# pc_healthypi_5_5.net
KiCad netlist of a schematic drawn in EAGLE
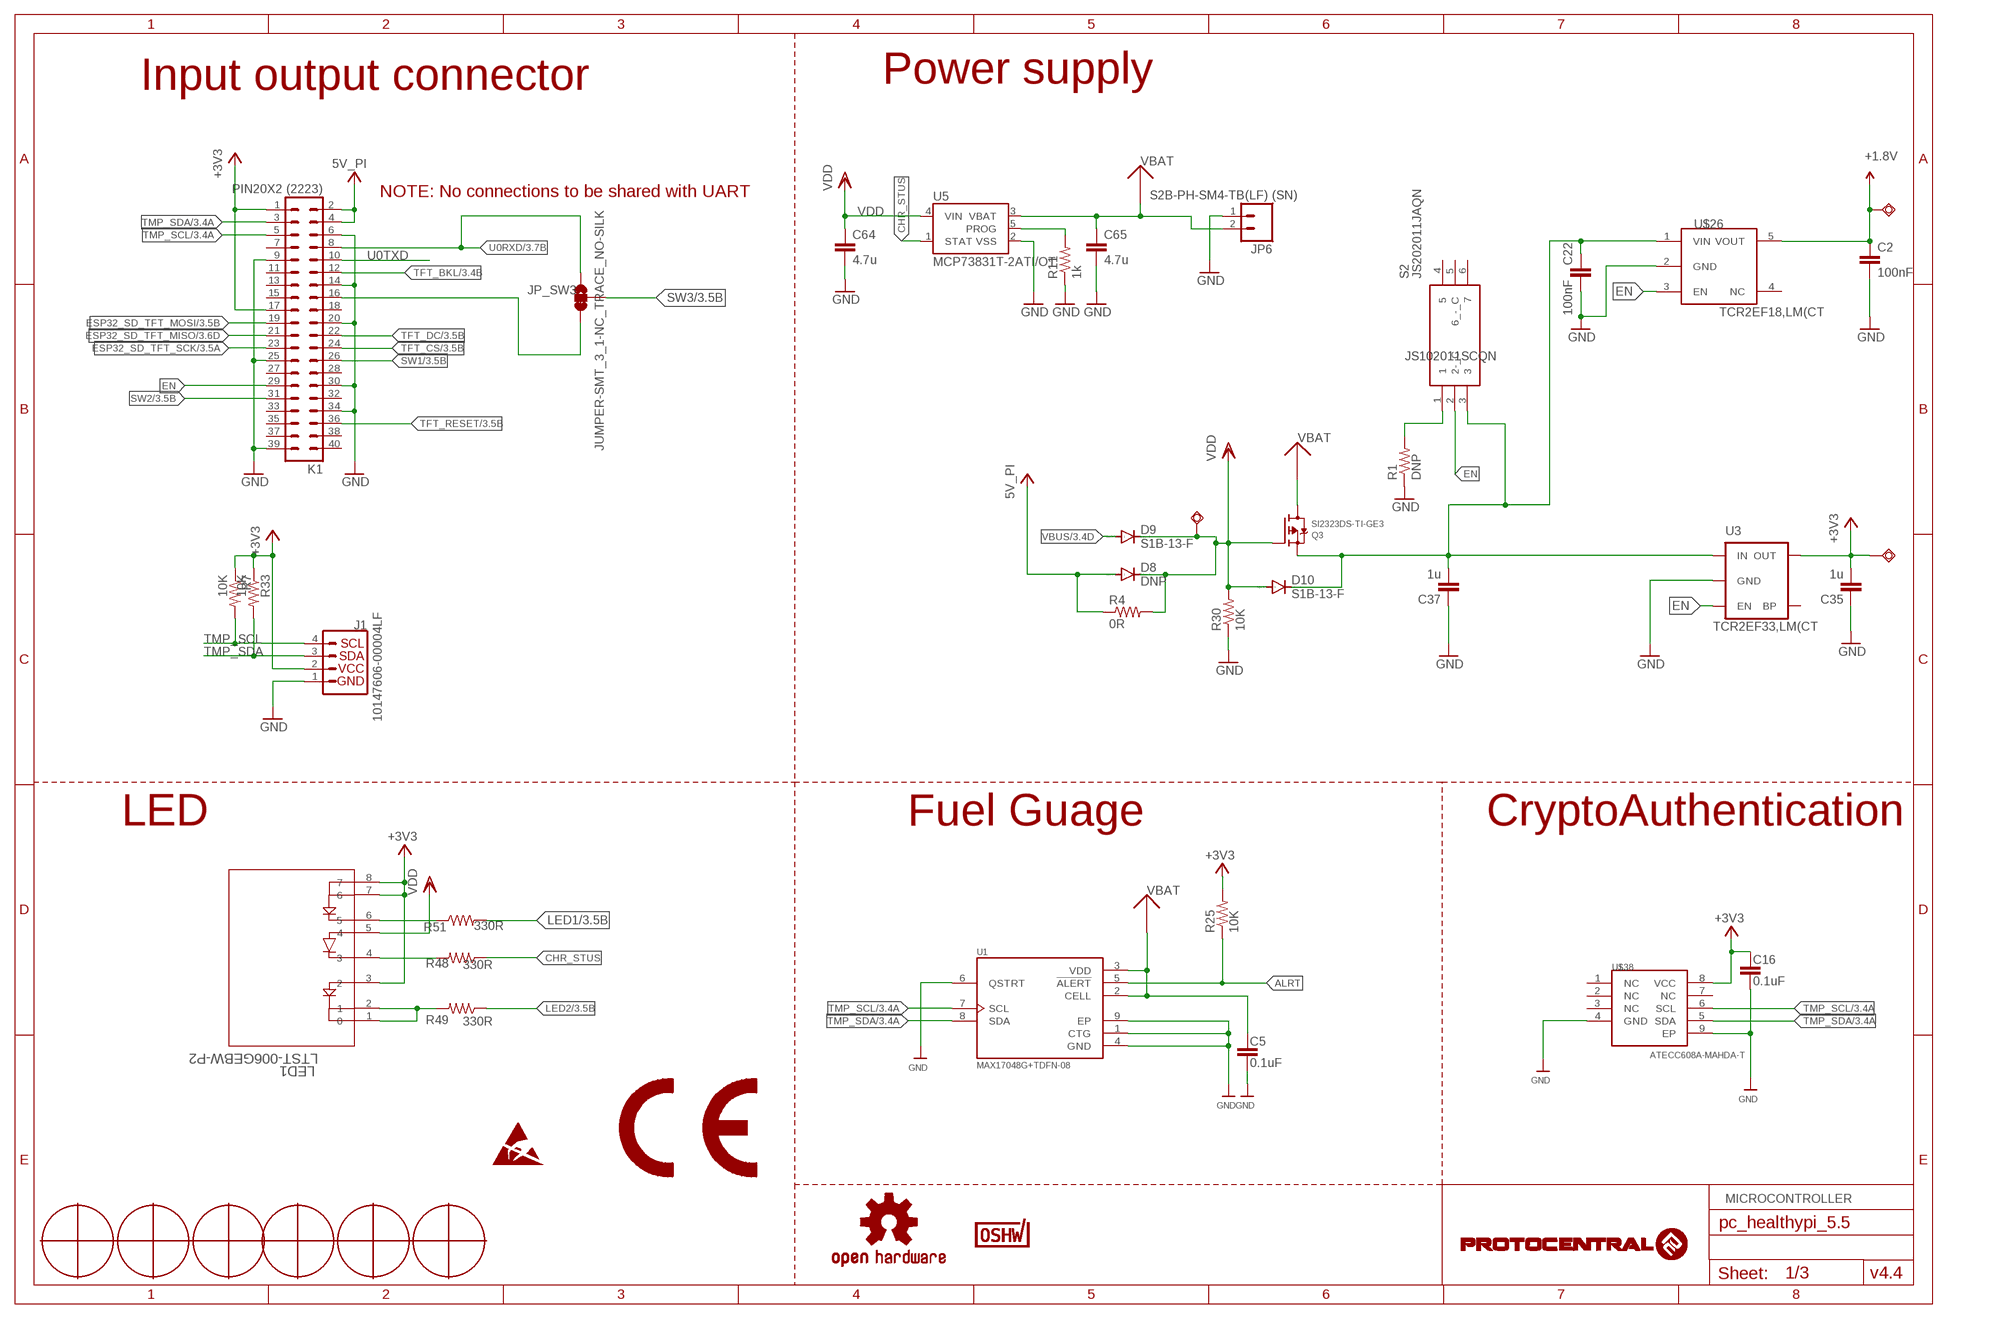
[diagram p0: schematic, sheet 1]
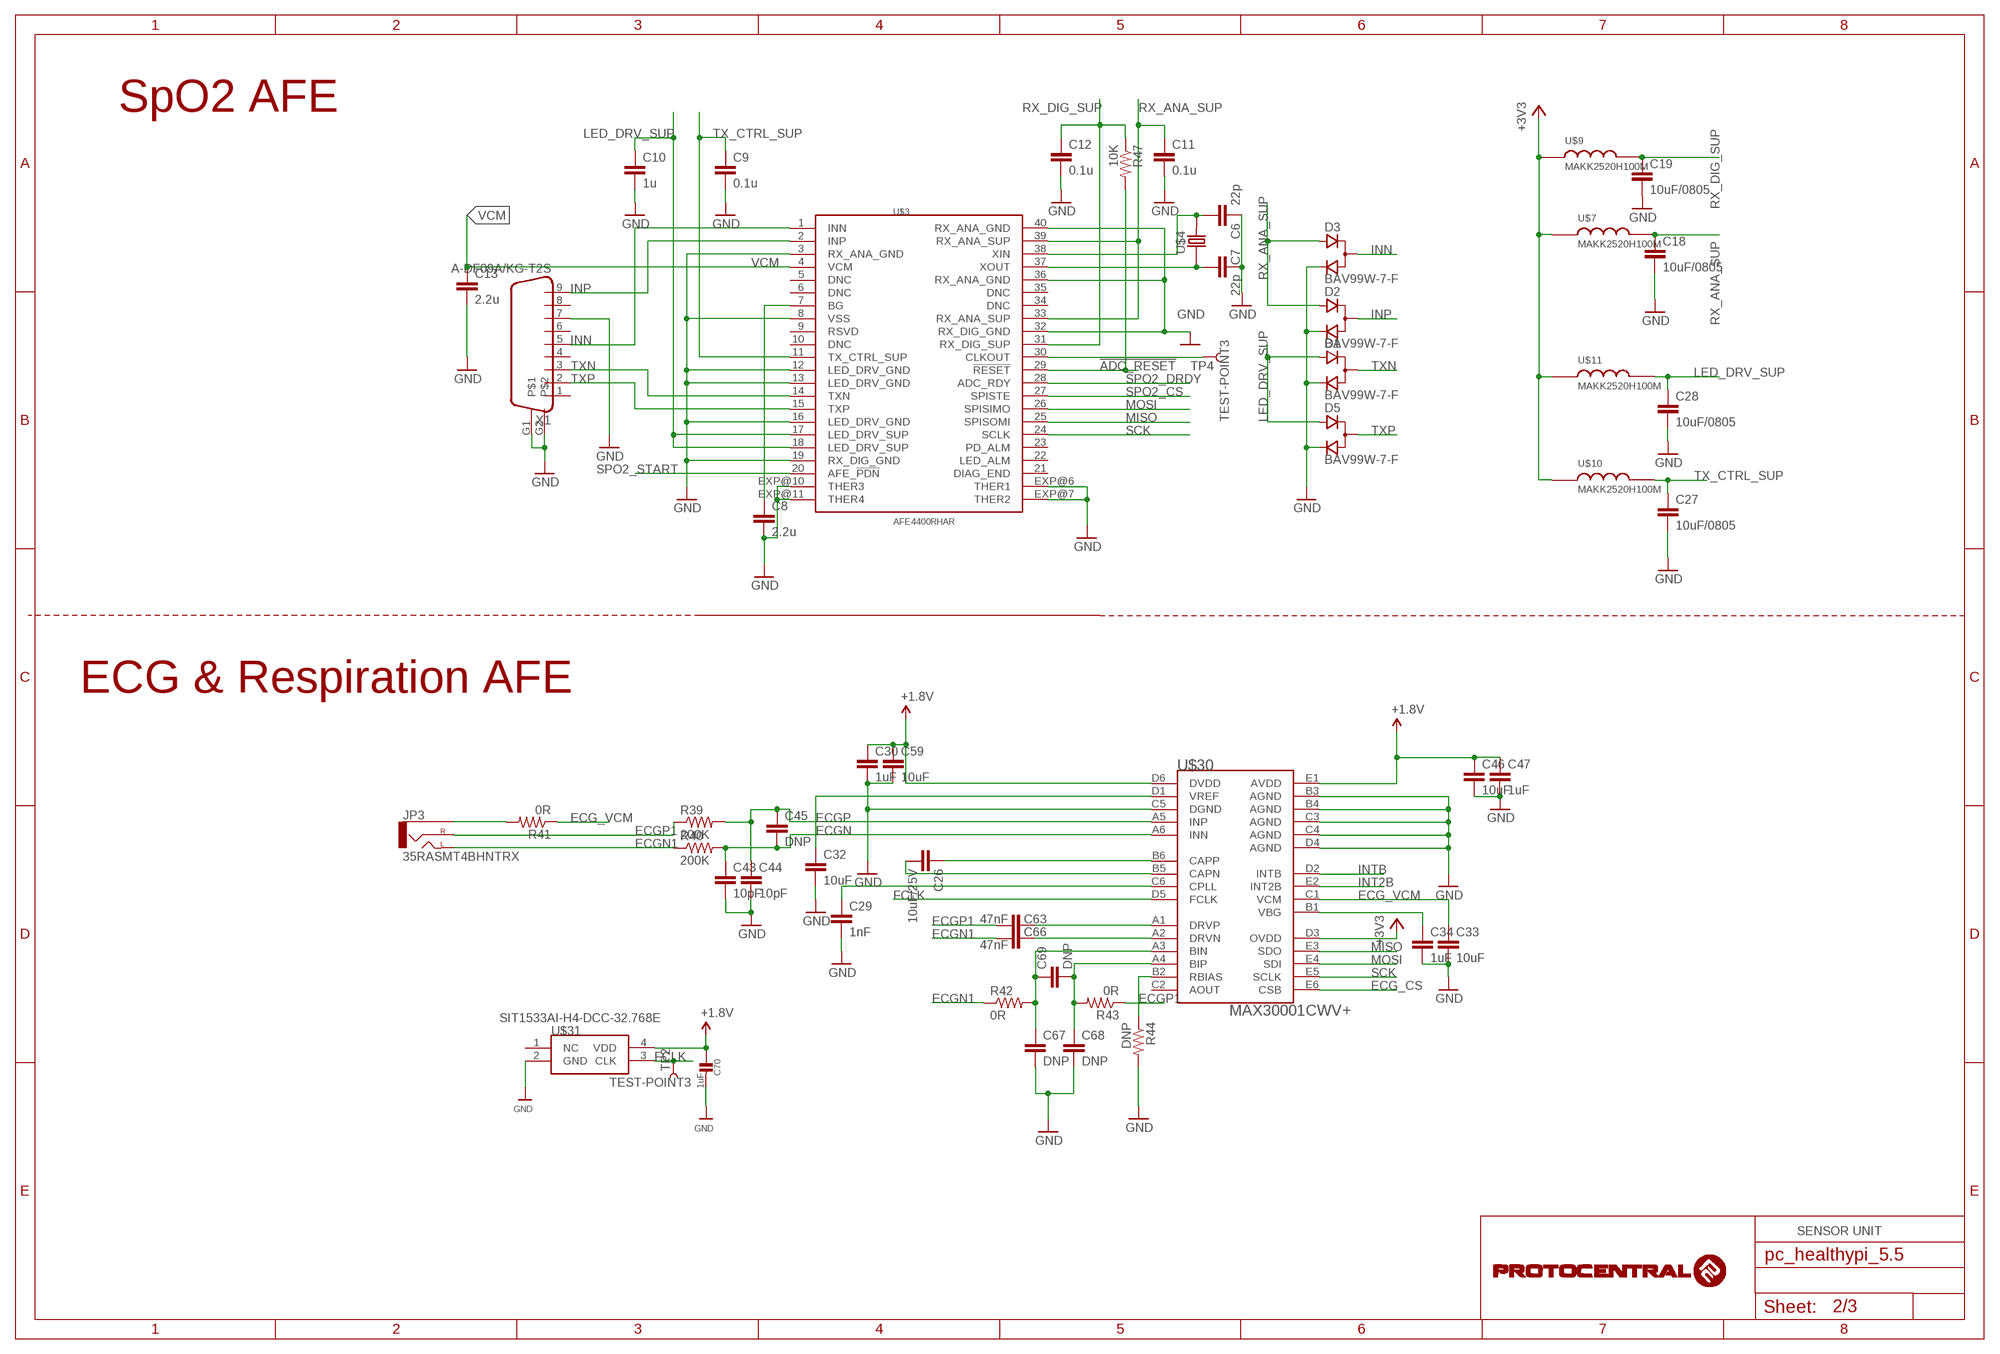
[diagram p1: schematic, sheet 2]
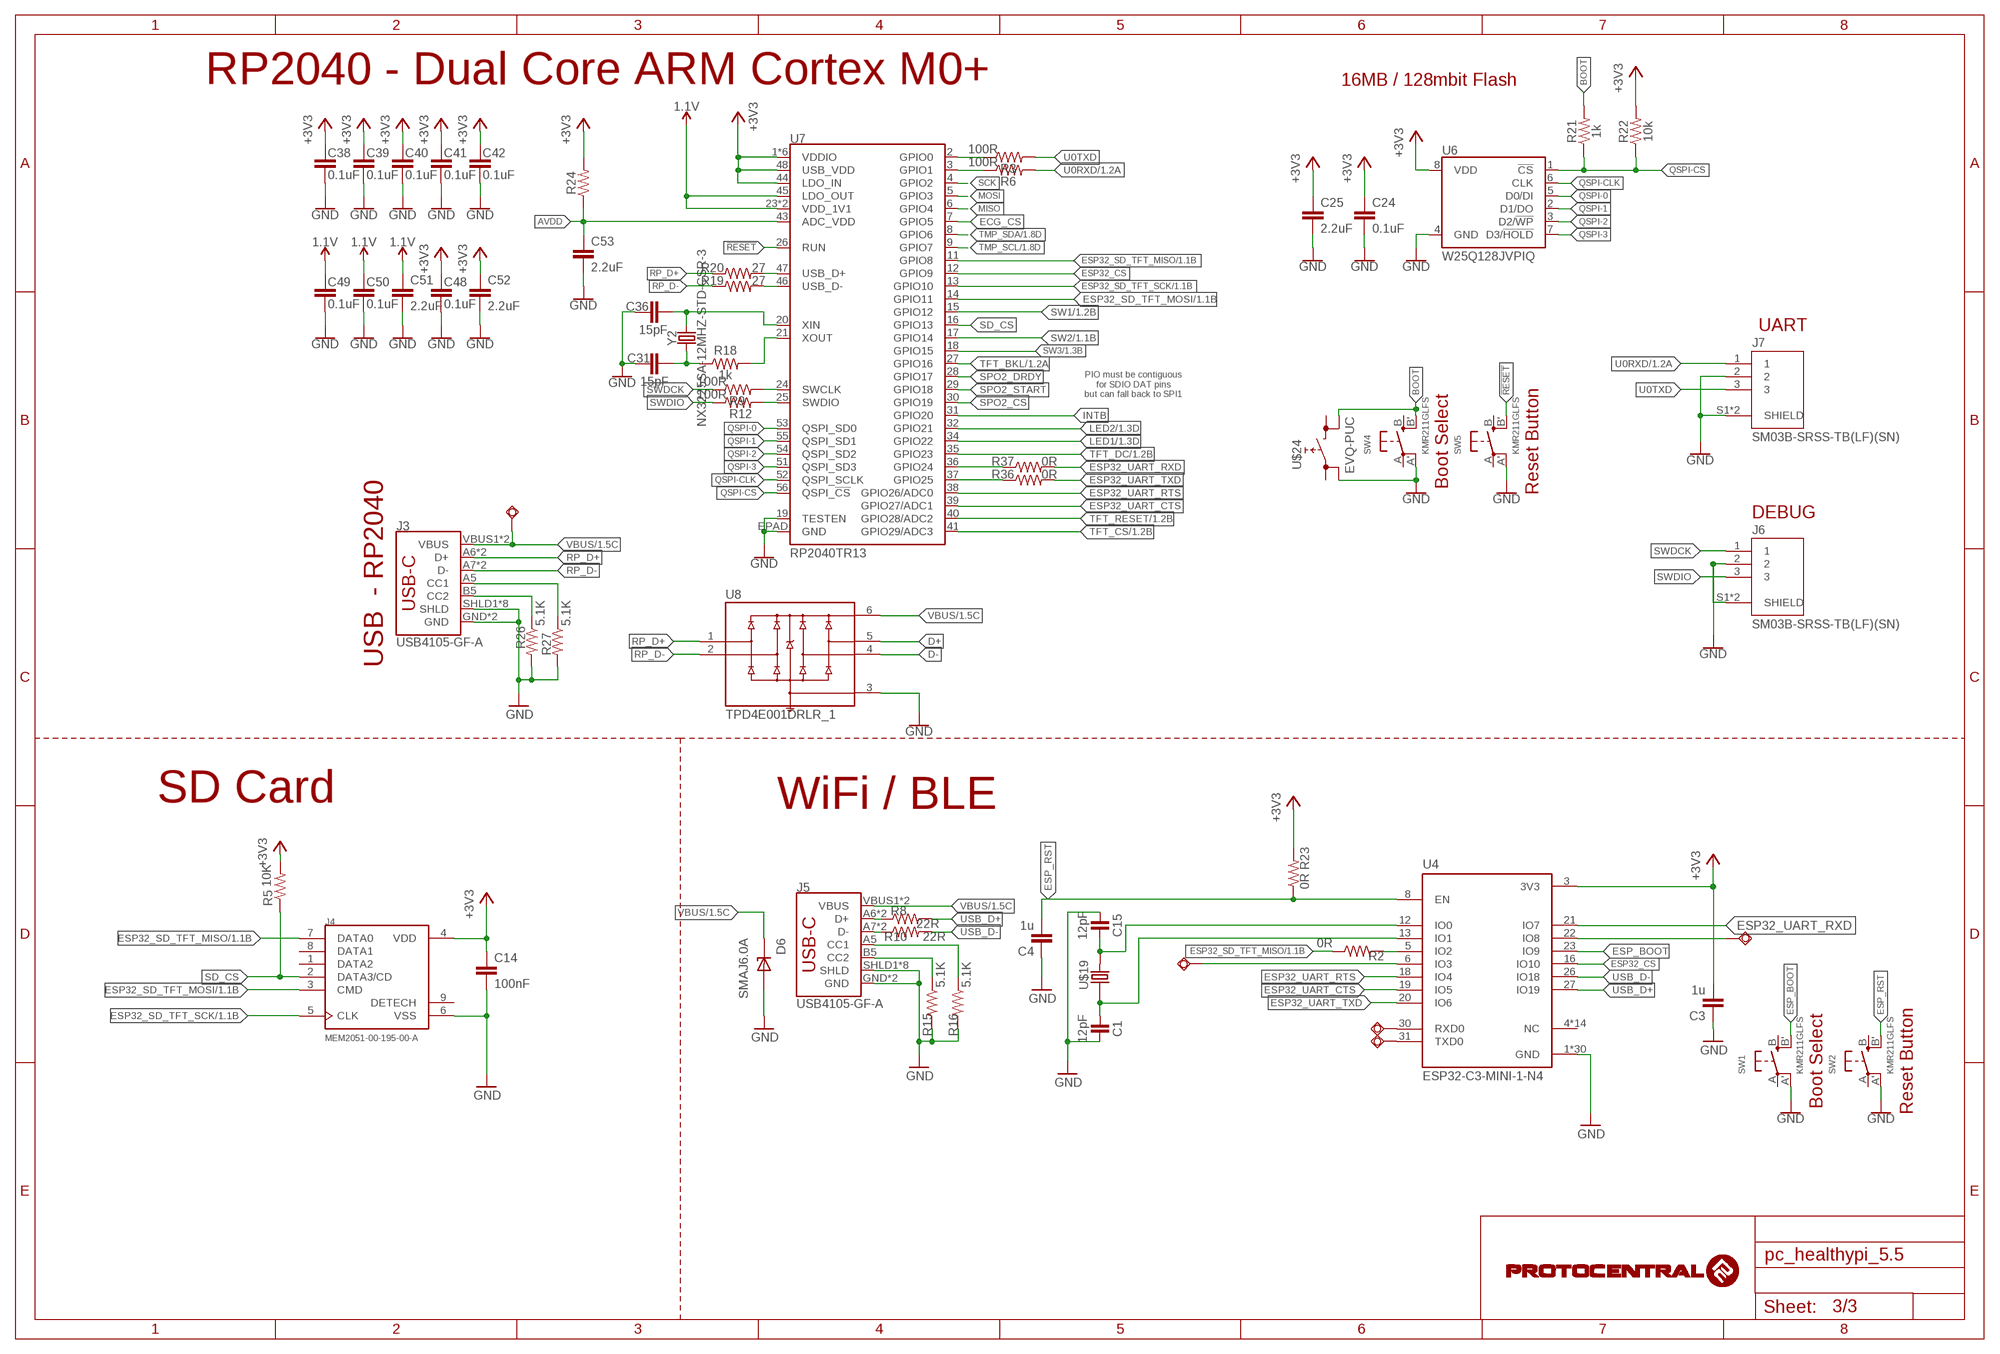
[diagram p2: schematic, sheet 3]

(export (version "E")
  (design (tool "Eeschema 10.0.6"))
  (components
    (comp (ref "C1")
      (value "12pF")
      (footprint "eagle-import:C0402")
      (libsource (lib "eagle-import") (part "CAPACITORS-0402"))
    )
    (comp (ref "C3")
      (value "1u")
      (footprint "eagle-import:C0402")
      (libsource (lib "eagle-import") (part "rcl_334_C-EUC0402"))
    )
    (comp (ref "C4")
      (value "1u")
      (footprint "eagle-import:C0402")
      (libsource (lib "eagle-import") (part "rcl_334_C-EUC0402"))
    )
    (comp (ref "C14")
      (value "100nF")
      (footprint "eagle-import:C0402")
      (libsource (lib "eagle-import") (part "C-EUC0402"))
    )
    (comp (ref "C15")
      (value "12pF")
      (footprint "eagle-import:C0402")
      (libsource (lib "eagle-import") (part "CAPACITORS-0402"))
    )
    (comp (ref "C24")
      (value "0.1uF")
      (footprint "eagle-import:0402-TIGHT")
      (libsource (lib "eagle-import") (part "0.1UF-0402T-6.3V-10%-X7R"))
    )
    (comp (ref "C25")
      (value "2.2uF")
      (footprint "eagle-import:0402-TIGHT")
      (libsource (lib "eagle-import") (part "2.2UF-0402_TIGHT-10V-10%-X5R"))
    )
    (comp (ref "C31")
      (value "15pF")
      (footprint "eagle-import:0402-TIGHT")
      (libsource (lib "eagle-import") (part "15PF-0402T-50V-5%"))
    )
    (comp (ref "C36")
      (value "15pF")
      (footprint "eagle-import:0402-TIGHT")
      (libsource (lib "eagle-import") (part "15PF-0402T-50V-5%"))
    )
    (comp (ref "C38")
      (value "0.1uF")
      (footprint "eagle-import:0402-TIGHT")
      (libsource (lib "eagle-import") (part "0.1UF-0402T-6.3V-10%-X7R"))
    )
    (comp (ref "C39")
      (value "0.1uF")
      (footprint "eagle-import:0402-TIGHT")
      (libsource (lib "eagle-import") (part "0.1UF-0402T-6.3V-10%-X7R"))
    )
    (comp (ref "C40")
      (value "0.1uF")
      (footprint "eagle-import:0402-TIGHT")
      (libsource (lib "eagle-import") (part "0.1UF-0402T-6.3V-10%-X7R"))
    )
    (comp (ref "C41")
      (value "0.1uF")
      (footprint "eagle-import:0402-TIGHT")
      (libsource (lib "eagle-import") (part "0.1UF-0402T-6.3V-10%-X7R"))
    )
    (comp (ref "C42")
      (value "0.1uF")
      (footprint "eagle-import:0402-TIGHT")
      (libsource (lib "eagle-import") (part "0.1UF-0402T-6.3V-10%-X7R"))
    )
    (comp (ref "C48")
      (value "0.1uF")
      (footprint "eagle-import:0402-TIGHT")
      (libsource (lib "eagle-import") (part "0.1UF-0402T-6.3V-10%-X7R"))
    )
    (comp (ref "C49")
      (value "0.1uF")
      (footprint "eagle-import:0402-TIGHT")
      (libsource (lib "eagle-import") (part "0.1UF-0402T-6.3V-10%-X7R"))
    )
    (comp (ref "C50")
      (value "0.1uF")
      (footprint "eagle-import:0402-TIGHT")
      (libsource (lib "eagle-import") (part "0.1UF-0402T-6.3V-10%-X7R"))
    )
    (comp (ref "C51")
      (value "2.2uF")
      (footprint "eagle-import:0402-TIGHT")
      (libsource (lib "eagle-import") (part "2.2UF-0402_TIGHT-10V-10%-X5R"))
    )
    (comp (ref "C52")
      (value "2.2uF")
      (footprint "eagle-import:0402-TIGHT")
      (libsource (lib "eagle-import") (part "2.2UF-0402_TIGHT-10V-10%-X5R"))
    )
    (comp (ref "C53")
      (value "2.2uF")
      (footprint "eagle-import:0402-TIGHT")
      (libsource (lib "eagle-import") (part "2.2UF-0402_TIGHT-10V-10%-X5R"))
    )
    (comp (ref "D6")
      (value "SMAJ6.0A")
      (footprint "eagle-import:DIOM4325X250N")
      (fields (field (name "DIGI-KEY_PART_NUMBER") "SMAJ6.0ALFTR-ND") (field (name "MF") "Littelfuse"))
      (libsource (lib "eagle-import") (part "SMAJ6.0A"))
    )
    (comp (ref "J3")
      (value "USB4105-GF-A")
      (footprint "eagle-import:USB-C-16P")
      (libsource (lib "eagle-import") (part "USB_C16PIN"))
    )
    (comp (ref "J4")
      (value "MEM2051-00-195-00-A")
      (footprint "eagle-import:GCT_MEM2051-00-195-00-A")
      (fields (field (name "MF") "Global Connector Technology"))
      (libsource (lib "eagle-import") (part "MEM2051-00-195-00-A"))
    )
    (comp (ref "J5")
      (value "USB4105-GF-A")
      (footprint "eagle-import:USB-C-16P")
      (libsource (lib "eagle-import") (part "circuitects_38825256_USB_C16PIN"))
    )
    (comp (ref "J6")
      (value "SM03B-SRSS-TB(LF)(SN)")
      (footprint "eagle-import:JST_SM03B-SRSS-TB(LF)(SN)")
      (fields (field (name "MF") "JST Sales America Inc."))
      (libsource (lib "eagle-import") (part "SM03B-SRSS-TB(LF)(SN)"))
    )
    (comp (ref "J7")
      (value "SM03B-SRSS-TB(LF)(SN)")
      (footprint "eagle-import:JST_SM03B-SRSS-TB(LF)(SN)")
      (fields (field (name "MF") "JST Sales America Inc."))
      (libsource (lib "eagle-import") (part "SM03B-SRSS-TB(LF)(SN)"))
    )
    (comp (ref "R2")
      (value "0R")
      (footprint "eagle-import:R0402")
      (libsource (lib "eagle-import") (part "rcl_334_R-US_R0402"))
    )
    (comp (ref "R3")
      (value "100R")
      (footprint "eagle-import:R0402")
      (libsource (lib "eagle-import") (part "rcl_334_R-US_R0402"))
    )
    (comp (ref "R5")
      (value "10K")
      (footprint "eagle-import:R0402")
      (libsource (lib "eagle-import") (part "R-US_R0402"))
    )
    (comp (ref "R6")
      (value "100R")
      (footprint "eagle-import:R0402")
      (libsource (lib "eagle-import") (part "rcl_334_R-US_R0402"))
    )
    (comp (ref "R8")
      (value "22R")
      (footprint "eagle-import:R0402")
      (libsource (lib "eagle-import") (part "rcl_334_R-US_R0402"))
    )
    (comp (ref "R9")
      (value "100R")
      (footprint "eagle-import:R0402")
      (libsource (lib "eagle-import") (part "rcl_334_R-US_R0402"))
    )
    (comp (ref "R10")
      (value "22R")
      (footprint "eagle-import:R0402")
      (libsource (lib "eagle-import") (part "rcl_334_R-US_R0402"))
    )
    (comp (ref "R12")
      (value "100R")
      (footprint "eagle-import:R0402")
      (libsource (lib "eagle-import") (part "rcl_334_R-US_R0402"))
    )
    (comp (ref "R15")
      (value "5.1K")
      (footprint "eagle-import:R0402")
      (libsource (lib "eagle-import") (part "rcl_334_R-US_R0402"))
    )
    (comp (ref "R16")
      (value "5.1K")
      (footprint "eagle-import:R0402")
      (libsource (lib "eagle-import") (part "rcl_334_R-US_R0402"))
    )
    (comp (ref "R18")
      (value "1k")
      (footprint "eagle-import:0402-TIGHT")
      (libsource (lib "eagle-import") (part "1KOHM-0402T-1/16W-1%"))
    )
    (comp (ref "R19")
      (value "27")
      (footprint "eagle-import:0402-TIGHT")
      (libsource (lib "eagle-import") (part "27OHM"))
    )
    (comp (ref "R20")
      (value "27")
      (footprint "eagle-import:0402-TIGHT")
      (libsource (lib "eagle-import") (part "27OHM"))
    )
    (comp (ref "R21")
      (value "1k")
      (footprint "eagle-import:0402-TIGHT")
      (libsource (lib "eagle-import") (part "1KOHM-0402T-1/16W-1%"))
    )
    (comp (ref "R22")
      (value "10k")
      (footprint "eagle-import:0402-TIGHT")
      (libsource (lib "eagle-import") (part "10KOHM-0402T-1/16W-1%"))
    )
    (comp (ref "R23")
      (value "0R")
      (footprint "eagle-import:R0402")
      (libsource (lib "eagle-import") (part "rcl_334_R-US_R0402"))
    )
    (comp (ref "R24")
      (value "200OHM-0402T-1/16W-1%")
      (footprint "eagle-import:0402-TIGHT")
      (libsource (lib "eagle-import") (part "200OHM-0402T-1/16W-1%"))
    )
    (comp (ref "R26")
      (value "5.1K")
      (footprint "eagle-import:R0402")
      (libsource (lib "eagle-import") (part "rcl_334_R-US_R0402"))
    )
    (comp (ref "R27")
      (value "5.1K")
      (footprint "eagle-import:R0402")
      (libsource (lib "eagle-import") (part "rcl_334_R-US_R0402"))
    )
    (comp (ref "R36")
      (value "0R")
      (footprint "eagle-import:0402-TIGHT")
      (libsource (lib "eagle-import") (part "27OHM"))
    )
    (comp (ref "R37")
      (value "0R")
      (footprint "eagle-import:0402-TIGHT")
      (libsource (lib "eagle-import") (part "27OHM"))
    )
    (comp (ref "SW1")
      (value "KMR211GLFS")
      (footprint "eagle-import:BTN_KMR2_4.6X2.8")
      (libsource (lib "eagle-import") (part "SWITCH_TACT_SMT4.6X2.8"))
    )
    (comp (ref "SW2")
      (value "KMR211GLFS")
      (footprint "eagle-import:BTN_KMR2_4.6X2.8")
      (libsource (lib "eagle-import") (part "SWITCH_TACT_SMT4.6X2.8"))
    )
    (comp (ref "SW4")
      (value "KMR211GLFS")
      (footprint "eagle-import:BTN_KMR2_4.6X2.8")
      (libsource (lib "eagle-import") (part "SWITCH_TACT_SMT4.6X2.8"))
    )
    (comp (ref "SW5")
      (value "KMR211GLFS")
      (footprint "eagle-import:BTN_KMR2_4.6X2.8")
      (libsource (lib "eagle-import") (part "SWITCH_TACT_SMT4.6X2.8"))
    )
    (comp (ref "SWIO2")
      (value "TPSQTP11R")
      (footprint "eagle-import:TP11R")
      (libsource (lib "eagle-import") (part "TPSQTP11R"))
    )
    (comp (ref "SWIO3")
      (value "TPSQTP11R")
      (footprint "eagle-import:TP11R")
      (libsource (lib "eagle-import") (part "TPSQTP11R"))
    )
    (comp (ref "SWIO8")
      (value "TPSQTP11R")
      (footprint "eagle-import:TP11R")
      (libsource (lib "eagle-import") (part "TPSQTP11R"))
    )
    (comp (ref "SWIO9")
      (value "TPSQTP11R")
      (footprint "eagle-import:TP11R")
      (libsource (lib "eagle-import") (part "TPSQTP11R"))
    )
    (comp (ref "TP5")
      (value "TPSQTP11R")
      (footprint "eagle-import:TP11R")
      (libsource (lib "eagle-import") (part "TPSQTP11R"))
    )
    (comp (ref "U$19")
      (value "520-327-12.5-34B(32.768KHZ)")
      (footprint "eagle-import:ECX-31B")
      (libsource (lib "eagle-import") (part "ECS-X-34B"))
    )
    (comp (ref "U$24")
      (value "EVQ-PUC")
      (footprint "eagle-import:EVQ-PUC")
      (libsource (lib "eagle-import") (part "EVQ-PUC"))
    )
    (comp (ref "U4")
      (value "ESP32-C3-MINI-1-N4")
      (footprint "eagle-import:XCVR_ESP32-C3-MINI-1-N4")
      (fields (field (name "MF") "Espressif Systems"))
      (libsource (lib "eagle-import") (part "ESP32-C3-MINI-1-N4"))
    )
    (comp (ref "U6")
      (value "W25Q128JVPIQ")
      (footprint "eagle-import:WSON-8-6X5-SKINNY_CENTERPAD")
      (libsource (lib "eagle-import") (part "W25QXX128MBIT-6X5-SKINNY_CENTER"))
    )
    (comp (ref "U7")
      (value "RP2040TR13")
      (footprint "eagle-import:QFN-56")
      (libsource (lib "eagle-import") (part "RP2040"))
    )
    (comp (ref "U8")
      (value "TPD4E001DRLR_1")
      (footprint "eagle-import:SOTFL50P160X60-6N")
      (fields
        (field (name "DIGI-KEY_PART_NUMBER") "296-21887-2-ND")
        (field (name "MF") "Texas Instruments")
        (field (name "MP") "TPD4E001DRLR")
      )
      (libsource (lib "eagle-import") (part "TPD4E001DRLR_1"))
    )
    (comp (ref "Y2")
      (value "NX3225SA-12MHZ-STD-CSR-3")
      (footprint "eagle-import:CRYSTAL-SMD-2X2.5MM")
      (libsource (lib "eagle-import") (part "CRYSTAL-12MHZ"))
    )
    (comp (ref "C6")
      (value "22p")
      (footprint "eagle-import:C0402")
      (libsource (lib "eagle-import") (part "rcl_334_C-EUC0402"))
    )
    (comp (ref "C7")
      (value "22p")
      (footprint "eagle-import:C0402")
      (libsource (lib "eagle-import") (part "rcl_334_C-EUC0402"))
    )
    (comp (ref "C8")
      (value "2.2u")
      (footprint "eagle-import:C0402")
      (libsource (lib "eagle-import") (part "rcl_334_C-EUC0402"))
    )
    (comp (ref "C9")
      (value "0.1u")
      (footprint "eagle-import:C0402")
      (libsource (lib "eagle-import") (part "rcl_334_C-EUC0402"))
    )
    (comp (ref "C10")
      (value "1u")
      (footprint "eagle-import:C0805")
      (libsource (lib "eagle-import") (part "rcl_334_C-EUC0805"))
    )
    (comp (ref "C11")
      (value "0.1u")
      (footprint "eagle-import:C0402")
      (libsource (lib "eagle-import") (part "rcl_334_C-EUC0402"))
    )
    (comp (ref "C12")
      (value "0.1u")
      (footprint "eagle-import:C0402")
      (libsource (lib "eagle-import") (part "rcl_334_C-EUC0402"))
    )
    (comp (ref "C13")
      (value "2.2u")
      (footprint "eagle-import:C0402")
      (libsource (lib "eagle-import") (part "rcl_334_C-EUC0402"))
    )
    (comp (ref "C18")
      (value "10uF/0805")
      (footprint "eagle-import:C0805")
      (libsource (lib "eagle-import") (part "rcl_334_C-EUC0805"))
    )
    (comp (ref "C19")
      (value "10uF/0805")
      (footprint "eagle-import:C0805")
      (libsource (lib "eagle-import") (part "rcl_334_C-EUC0805"))
    )
    (comp (ref "C26")
      (value "10uF/25V")
      (footprint "eagle-import:C0805")
      (libsource (lib "eagle-import") (part "rcl_334_C-EUC0805"))
    )
    (comp (ref "C27")
      (value "10uF/0805")
      (footprint "eagle-import:C0805")
      (libsource (lib "eagle-import") (part "rcl_334_C-EUC0805"))
    )
    (comp (ref "C28")
      (value "10uF/0805")
      (footprint "eagle-import:C0805")
      (libsource (lib "eagle-import") (part "rcl_334_C-EUC0805"))
    )
    (comp (ref "C29")
      (value "1nF")
      (footprint "eagle-import:C0402")
      (libsource (lib "eagle-import") (part "rcl_334_C-EUC0402"))
    )
    (comp (ref "C30")
      (value "1uF")
      (footprint "eagle-import:C0402")
      (libsource (lib "eagle-import") (part "rcl_334_C-EUC0402"))
    )
    (comp (ref "C32")
      (value "10uF")
      (footprint "eagle-import:C0805")
      (libsource (lib "eagle-import") (part "rcl_334_C-EUC0805"))
    )
    (comp (ref "C33")
      (value "10uF")
      (footprint "eagle-import:C0805")
      (libsource (lib "eagle-import") (part "rcl_334_C-EUC0805"))
    )
    (comp (ref "C34")
      (value "1uF")
      (footprint "eagle-import:C0402")
      (libsource (lib "eagle-import") (part "rcl_334_C-EUC0402"))
    )
    (comp (ref "C43")
      (value "10pF")
      (footprint "eagle-import:C0402")
      (libsource (lib "eagle-import") (part "rcl_334_C-EUC0402"))
    )
    (comp (ref "C44")
      (value "10pF")
      (footprint "eagle-import:C0402")
      (libsource (lib "eagle-import") (part "rcl_334_C-EUC0402"))
    )
    (comp (ref "C45")
      (value "DNP")
      (footprint "eagle-import:C0402")
      (libsource (lib "eagle-import") (part "rcl_334_C-EUC0402"))
    )
    (comp (ref "C46")
      (value "10uF")
      (footprint "eagle-import:C0805")
      (libsource (lib "eagle-import") (part "rcl_334_C-EUC0805"))
    )
    (comp (ref "C47")
      (value "1uF")
      (footprint "eagle-import:C0402")
      (libsource (lib "eagle-import") (part "rcl_334_C-EUC0402"))
    )
    (comp (ref "C59")
      (value "10uF")
      (footprint "eagle-import:C0805")
      (libsource (lib "eagle-import") (part "rcl_334_C-EUC0805"))
    )
    (comp (ref "C63")
      (value "47nF")
      (footprint "eagle-import:C0402")
      (libsource (lib "eagle-import") (part "rcl_334_C-EUC0402"))
    )
    (comp (ref "C66")
      (value "47nF")
      (footprint "eagle-import:C0402")
      (libsource (lib "eagle-import") (part "rcl_334_C-EUC0402"))
    )
    (comp (ref "C67")
      (value "DNP")
      (footprint "eagle-import:C0402")
      (libsource (lib "eagle-import") (part "rcl_334_C-EUC0402"))
    )
    (comp (ref "C68")
      (value "DNP")
      (footprint "eagle-import:C0402")
      (libsource (lib "eagle-import") (part "rcl_334_C-EUC0402"))
    )
    (comp (ref "C69")
      (value "DNP")
      (footprint "eagle-import:C0402")
      (libsource (lib "eagle-import") (part "rcl_334_C-EUC0402"))
    )
    (comp (ref "C70")
      (value "1uF")
      (footprint "eagle-import:0402")
      (libsource (lib "eagle-import") (part "CAP_CERAMIC0402"))
    )
    (comp (ref "D1")
      (value "BAV99W-7-F")
      (footprint "eagle-import:SOT323")
      (libsource (lib "eagle-import") (part "D_ACACSOT323"))
    )
    (comp (ref "D2")
      (value "BAV99W-7-F")
      (footprint "eagle-import:SOT323")
      (libsource (lib "eagle-import") (part "D_ACACSOT323"))
    )
    (comp (ref "D3")
      (value "BAV99W-7-F")
      (footprint "eagle-import:SOT323")
      (libsource (lib "eagle-import") (part "D_ACACSOT323"))
    )
    (comp (ref "D5")
      (value "BAV99W-7-F")
      (footprint "eagle-import:SOT323")
      (libsource (lib "eagle-import") (part "D_ACACSOT323"))
    )
    (comp (ref "JP3")
      (value "35RASMT4BHNTRX")
      (footprint "eagle-import:AUDIO-JACK-3.5MM-SMD")
      (libsource (lib "eagle-import") (part "AUDIO-JACKSMD2"))
    )
    (comp (ref "R39")
      (value "200K")
      (footprint "eagle-import:0805")
      (libsource (lib "eagle-import") (part "RESISTOR0805-RES"))
    )
    (comp (ref "R40")
      (value "200K")
      (footprint "eagle-import:0805")
      (libsource (lib "eagle-import") (part "RESISTOR0805-RES"))
    )
    (comp (ref "R41")
      (value "0R")
      (footprint "eagle-import:0805")
      (libsource (lib "eagle-import") (part "RESISTOR0805-RES"))
    )
    (comp (ref "R42")
      (value "0R")
      (footprint "eagle-import:0402-RES")
      (libsource (lib "eagle-import") (part "RESISTOR0402-RES"))
    )
    (comp (ref "R43")
      (value "0R")
      (footprint "eagle-import:0402-RES")
      (libsource (lib "eagle-import") (part "RESISTOR0402-RES"))
    )
    (comp (ref "R44")
      (value "DNP")
      (footprint "eagle-import:0402-RES")
      (libsource (lib "eagle-import") (part "RESISTOR0402-RES"))
    )
    (comp (ref "R47")
      (value "10K")
      (footprint "eagle-import:R0402")
      (libsource (lib "eagle-import") (part "rcl_334_R-US_R0402"))
    )
    (comp (ref "TP2")
      (value "TEST-POINT3")
      (footprint "eagle-import:PAD.03X.03")
      (libsource (lib "eagle-import") (part "TEST-POINT3"))
    )
    (comp (ref "TP4")
      (value "TEST-POINT3")
      (footprint "eagle-import:PAD.03X.03")
      (libsource (lib "eagle-import") (part "TEST-POINT3"))
    )
    (comp (ref "U$3")
      (value "AFE4400RHAR")
      (footprint "eagle-import:QFN-40")
      (libsource (lib "eagle-import") (part "AFE4400"))
    )
    (comp (ref "U$4")
      (value "ABM3")
      (footprint "eagle-import:ABM3")
      (libsource (lib "eagle-import") (part "ABM3"))
    )
    (comp (ref "U$7")
      (value "MAKK2520H100M")
      (footprint "eagle-import:LPS")
      (libsource (lib "eagle-import") (part "LPS"))
    )
    (comp (ref "U$9")
      (value "MAKK2520H100M")
      (footprint "eagle-import:LPS")
      (libsource (lib "eagle-import") (part "LPS"))
    )
    (comp (ref "U$10")
      (value "MAKK2520H100M")
      (footprint "eagle-import:LPS")
      (libsource (lib "eagle-import") (part "LPS"))
    )
    (comp (ref "U$11")
      (value "MAKK2520H100M")
      (footprint "eagle-import:LPS")
      (libsource (lib "eagle-import") (part "LPS"))
    )
    (comp (ref "U$30")
      (value "MAX30001CWV+")
      (footprint "eagle-import:30WLP")
      (libsource (lib "eagle-import") (part "MAX30001CWV+"))
    )
    (comp (ref "U$31")
      (value "SIT1533AI-H4-DCC-32.768E")
      (footprint "eagle-import:SIT1533")
      (libsource (lib "eagle-import") (part "SIT1533"))
    )
    (comp (ref "X1")
      (value "A-DF09A/KG-T2S")
      (footprint "eagle-import:DB9")
      (libsource (lib "eagle-import") (part "DB9"))
    )
    (comp (ref "C2")
      (value "100nF")
      (footprint "eagle-import:C0402")
      (libsource (lib "eagle-import") (part "rcl_334_C-EUC0402"))
    )
    (comp (ref "C5")
      (value "0.1uF")
      (footprint "eagle-import:0402-TIGHT")
      (libsource (lib "eagle-import") (part "0.1UF-0402T-6.3V-10%-X7R"))
    )
    (comp (ref "C16")
      (value "0.1uF")
      (footprint "eagle-import:0402-TIGHT")
      (libsource (lib "eagle-import") (part "0.1UF-0402T-6.3V-10%-X7R"))
    )
    (comp (ref "C22")
      (value "100nF")
      (footprint "eagle-import:C0402")
      (libsource (lib "eagle-import") (part "rcl_334_C-EUC0402"))
    )
    (comp (ref "C35")
      (value "1u")
      (footprint "eagle-import:C0402")
      (libsource (lib "eagle-import") (part "rcl_334_C-EUC0402"))
    )
    (comp (ref "C37")
      (value "1u")
      (footprint "eagle-import:C0402")
      (libsource (lib "eagle-import") (part "rcl_334_C-EUC0402"))
    )
    (comp (ref "C64")
      (value "4.7u")
      (footprint "eagle-import:C0805")
      (libsource (lib "eagle-import") (part "rcl_334_C-EUC0805"))
    )
    (comp (ref "C65")
      (value "4.7u")
      (footprint "eagle-import:C0805")
      (libsource (lib "eagle-import") (part "rcl_334_C-EUC0805"))
    )
    (comp (ref "D8")
      (value "DNP")
      (footprint "eagle-import:SOD-123_MINI-SMA")
      (libsource (lib "eagle-import") (part "CGRM400-G1"))
    )
    (comp (ref "D9")
      (value "S1B-13-F")
      (footprint "eagle-import:SOD-123_MINI-SMA")
      (libsource (lib "eagle-import") (part "CGRM400-G1"))
    )
    (comp (ref "D10")
      (value "S1B-13-F")
      (footprint "eagle-import:SOD-123_MINI-SMA")
      (libsource (lib "eagle-import") (part "CGRM400-G1"))
    )
    (comp (ref "J1")
      (value "10147606-00004LF")
      (footprint "eagle-import:JST04_1MM_RA")
      (libsource (lib "eagle-import") (part "QWIIC_CONNECTORJS-1MM"))
    )
    (comp (ref "JP6")
      (value "S2B-PH-SM4-TB(LF) (SN)")
      (footprint "eagle-import:JST-2-SMD")
      (libsource (lib "eagle-import") (part "M02-JST-2MM-SMT"))
    )
    (comp (ref "JP_SW3")
      (value "JUMPER-SMT_3_1-NC_TRACE_NO-SILK")
      (footprint "eagle-import:SMT-JUMPER_3_1-NC_TRACE_NO-SILK")
      (libsource (lib "eagle-import") (part "JUMPER-SMT_3_1-NC_TRACE_NO-SILK"))
    )
    (comp (ref "K1")
      (value "PIN20X2 (2223)")
      (footprint "eagle-import:PIN_20X2")
      (libsource (lib "eagle-import") (part "PIN20X2"))
    )
    (comp (ref "LED1")
      (value "LTST-006GEBW-P2")
      (footprint "eagle-import:LTST-008BGEW_LTO")
      (fields (field (name "COPYRIGHT") "Copyright (C) 2023 Ultra Librarian. All rights reserved."))
      (libsource (lib "eagle-import") (part "LTST-006GEBW-P2"))
    )
    (comp (ref "Q3")
      (value "SI2323DS-TI-GE3")
      (footprint "eagle-import:SOT23-R")
      (libsource (lib "eagle-import") (part "MOSFET-P"))
    )
    (comp (ref "R1")
      (value "DNP")
      (footprint "eagle-import:R0402")
      (libsource (lib "eagle-import") (part "rcl_334_R-US_R0402"))
    )
    (comp (ref "R4")
      (value "0R")
      (footprint "eagle-import:0805")
      (libsource (lib "eagle-import") (part "RESISTOR0805-RES"))
    )
    (comp (ref "R7")
      (value "10K")
      (footprint "eagle-import:R0402")
      (libsource (lib "eagle-import") (part "rcl_334_R-US_R0402"))
    )
    (comp (ref "R11")
      (value "1k")
      (footprint "eagle-import:R0402")
      (libsource (lib "eagle-import") (part "rcl_334_R-US_R0402"))
    )
    (comp (ref "R25")
      (value "10K")
      (footprint "eagle-import:0402-RES")
      (libsource (lib "eagle-import") (part "RESISTOR0402-RES"))
    )
    (comp (ref "R30")
      (value "10K")
      (footprint "eagle-import:R0402")
      (libsource (lib "eagle-import") (part "rcl_334_R-US_R0402"))
    )
    (comp (ref "R33")
      (value "10K")
      (footprint "eagle-import:R0402")
      (libsource (lib "eagle-import") (part "rcl_334_R-US_R0402"))
    )
    (comp (ref "R48")
      (value "330R")
      (footprint "eagle-import:0402-RES")
      (libsource (lib "eagle-import") (part "RESISTOR0402-RES"))
    )
    (comp (ref "R49")
      (value "330R")
      (footprint "eagle-import:0402-RES")
      (libsource (lib "eagle-import") (part "RESISTOR0402-RES"))
    )
    (comp (ref "R51")
      (value "330R")
      (footprint "eagle-import:0402-RES")
      (libsource (lib "eagle-import") (part "RESISTOR0402-RES"))
    )
    (comp (ref "S2")
      (value "JS202011JAQN")
      (footprint "eagle-import:JS202011JAQN")
      (fields (field (name "MF") "C&K"))
      (libsource (lib "eagle-import") (part "JS202011JAQN"))
    )
    (comp (ref "SWIO1")
      (value "TPSQTP11R")
      (footprint "eagle-import:TP11R")
      (libsource (lib "eagle-import") (part "TPSQTP11R"))
    )
    (comp (ref "SWIO5")
      (value "TPSQTP11R")
      (footprint "eagle-import:TP11R")
      (libsource (lib "eagle-import") (part "TPSQTP11R"))
    )
    (comp (ref "SWIO7")
      (value "TPSQTP11R")
      (footprint "eagle-import:TP11R")
      (libsource (lib "eagle-import") (part "TPSQTP11R"))
    )
    (comp (ref "U$1")
      (value "FUDCIALPOINTS")
      (footprint "eagle-import:FIDUCIALPOINTS")
      (libsource (lib "eagle-import") (part "circuitects_38825256_FUDCIALPOINTS"))
    )
    (comp (ref "U$5")
      (value "OSHW-LOGOM")
      (footprint "eagle-import:OSHW-LOGO-M")
      (libsource (lib "eagle-import") (part "OSHW-LOGOM"))
    )
    (comp (ref "U$13")
      (value "CERT-SMALL")
      (footprint "eagle-import:CERT-SMALL-SILK")
      (libsource (lib "eagle-import") (part "CERT-SMALL"))
    )
    (comp (ref "U$21")
      (value "FUDCIALPOINTS")
      (footprint "eagle-import:FIDUCIALPOINTS")
      (libsource (lib "eagle-import") (part "FUDCIALPOINTS"))
    )
    (comp (ref "U$23")
      (value "FUDCIALPOINTS")
      (footprint "eagle-import:FIDUCIALPOINTS")
      (libsource (lib "eagle-import") (part "circuitects_38825256_FUDCIALPOINTS"))
    )
    (comp (ref "U$25")
      (value "FUDCIALPOINTS")
      (footprint "eagle-import:FIDUCIALPOINTS")
      (libsource (lib "eagle-import") (part "circuitects_38825256_FUDCIALPOINTS"))
    )
    (comp (ref "U$26")
      (value "TCR2EF18,LM(CT")
      (footprint "eagle-import:SOT95P285X140-5N")
      (libsource (lib "eagle-import") (part "AP7354D-18W5-7"))
    )
    (comp (ref "U$28")
      (value "FUDCIALPOINTS")
      (footprint "eagle-import:FIDUCIALPOINTS")
      (libsource (lib "eagle-import") (part "FUDCIALPOINTS"))
    )
    (comp (ref "U$29")
      (value "FUDCIALPOINTS")
      (footprint "eagle-import:FIDUCIALPOINTS")
      (libsource (lib "eagle-import") (part "FUDCIALPOINTS"))
    )
    (comp (ref "U$38")
      (value "ATECC608A-MAHDA-T")
      (footprint "eagle-import:PSON50P200X300X60-9N")
      (libsource (lib "eagle-import") (part "ATECC608B-TFLXTLS"))
    )
    (comp (ref "U1")
      (value "MAX17048G+TDFN-08")
      (footprint "eagle-import:SON50P200X200X80-9N")
      (fields (field (name "MF") "Analog Devices") (field (name "MP") "MAX17048G+"))
      (libsource (lib "eagle-import") (part "MAX17048G+TDFN-08"))
    )
    (comp (ref "U3")
      (value "TCR2EF33,LM(CT")
      (footprint "eagle-import:SOT23-5")
      (libsource (lib "eagle-import") (part "V_REG_LDOSMD"))
    )
    (comp (ref "U5")
      (value "MCP73831T-2ATI/OT")
      (footprint "eagle-import:SOT23-5")
      (libsource (lib "eagle-import") (part "MCP73831"))
    )
  )
  (nets
    (net (code "1") (name "+1.8V") (class "Default")
      (node (ref "C2") (pin "1") (pinfunction "1_1") (pintype "passive"))
      (node (ref "C30") (pin "1") (pinfunction "1_1") (pintype "passive"))
      (node (ref "C46") (pin "1") (pinfunction "1_1") (pintype "passive"))
      (node (ref "C47") (pin "1") (pinfunction "1_1") (pintype "passive"))
      (node (ref "C59") (pin "1") (pinfunction "1_1") (pintype "passive"))
      (node (ref "C70") (pin "1") (pinfunction "P$1_1") (pintype "passive"))
      (node (ref "SWIO5") (pin "TP") (pinfunction "TP_TP") (pintype "input"))
      (node (ref "U$26") (pin "5") (pinfunction "VOUT_5") (pintype "bidirectional"))
      (node (ref "U$30") (pin "D6") (pinfunction "DVDD_D6") (pintype "bidirectional"))
      (node (ref "U$30") (pin "E1") (pinfunction "AVDD_E1") (pintype "bidirectional"))
      (node (ref "U$31") (pin "4") (pinfunction "VDD_4") (pintype "bidirectional"))
    )
    (net (code "2") (name "+3V3") (class "Default")
      (node (ref "C14") (pin "1") (pinfunction "1_1") (pintype "passive"))
      (node (ref "C16") (pin "1") (pinfunction "1_1") (pintype "passive"))
      (node (ref "C24") (pin "1") (pinfunction "1_1") (pintype "passive"))
      (node (ref "C25") (pin "1") (pinfunction "1_1") (pintype "passive"))
      (node (ref "C3") (pin "2") (pinfunction "2_2") (pintype "passive"))
      (node (ref "C35") (pin "2") (pinfunction "2_2") (pintype "passive"))
      (node (ref "C38") (pin "1") (pinfunction "1_1") (pintype "passive"))
      (node (ref "C39") (pin "1") (pinfunction "1_1") (pintype "passive"))
      (node (ref "C40") (pin "1") (pinfunction "1_1") (pintype "passive"))
      (node (ref "C41") (pin "1") (pinfunction "1_1") (pintype "passive"))
      (node (ref "C42") (pin "1") (pinfunction "1_1") (pintype "passive"))
      (node (ref "C48") (pin "1") (pinfunction "1_1") (pintype "passive"))
      (node (ref "C52") (pin "1") (pinfunction "1_1") (pintype "passive"))
      (node (ref "J1") (pin "2") (pinfunction "2_2") (pintype "power_in"))
      (node (ref "J4") (pin "4") (pinfunction "VDD_4") (pintype "power_in"))
      (node (ref "K1") (pin "1") (pinfunction "1_1") (pintype "passive"))
      (node (ref "K1") (pin "17") (pinfunction "17_17") (pintype "passive"))
      (node (ref "LED1") (pin "3") (pinfunction "2_3") (pintype "passive"))
      (node (ref "LED1") (pin "7") (pinfunction "6_7") (pintype "passive"))
      (node (ref "LED1") (pin "8") (pinfunction "7_8") (pintype "passive"))
      (node (ref "R22") (pin "2") (pinfunction "2_2") (pintype "passive"))
      (node (ref "R23") (pin "2") (pinfunction "2_2") (pintype "passive"))
      (node (ref "R24") (pin "2") (pinfunction "2_2") (pintype "passive"))
      (node (ref "R25") (pin "2") (pinfunction "2_2") (pintype "passive"))
      (node (ref "R33") (pin "1") (pinfunction "1_1") (pintype "passive"))
      (node (ref "R5") (pin "2") (pinfunction "2_2") (pintype "passive"))
      (node (ref "R7") (pin "1") (pinfunction "1_1") (pintype "passive"))
      (node (ref "SWIO1") (pin "TP") (pinfunction "TP_TP") (pintype "input"))
      (node (ref "U$10") (pin "1") (pinfunction "P$1_1") (pintype "bidirectional"))
      (node (ref "U$11") (pin "1") (pinfunction "P$1_1") (pintype "bidirectional"))
      (node (ref "U$30") (pin "D3") (pinfunction "OVDD_D3") (pintype "bidirectional"))
      (node (ref "U$38") (pin "8") (pinfunction "VCC_8") (pintype "bidirectional"))
      (node (ref "U$7") (pin "1") (pinfunction "P$1_1") (pintype "bidirectional"))
      (node (ref "U$9") (pin "1") (pinfunction "P$1_1") (pintype "bidirectional"))
      (node (ref "U3") (pin "5") (pinfunction "OUT_5") (pintype "passive"))
      (node (ref "U4") (pin "3") (pinfunction "3V3_3") (pintype "power_in"))
      (node (ref "U6") (pin "8") (pinfunction "VDD_8") (pintype "bidirectional"))
      (node (ref "U7") (pin "1") (pinfunction "VDDIO_1") (pintype "bidirectional"))
      (node (ref "U7") (pin "10") (pinfunction "VDDIO_10") (pintype "bidirectional"))
      (node (ref "U7") (pin "22") (pinfunction "VDDIO_22") (pintype "bidirectional"))
      (node (ref "U7") (pin "33") (pinfunction "VDDIO_33") (pintype "bidirectional"))
      (node (ref "U7") (pin "42") (pinfunction "VDDIO_42") (pintype "bidirectional"))
      (node (ref "U7") (pin "44") (pinfunction "LDO_IN_44") (pintype "bidirectional"))
      (node (ref "U7") (pin "48") (pinfunction "USB_VDD_48") (pintype "bidirectional"))
      (node (ref "U7") (pin "49") (pinfunction "VDDIO_49") (pintype "bidirectional"))
    )
    (net (code "3") (name "+5V") (class "Default")
      (node (ref "D8") (pin "A") (pinfunction "A_A") (pintype "passive"))
      (node (ref "K1") (pin "2") (pinfunction "2_2") (pintype "passive"))
      (node (ref "K1") (pin "4") (pinfunction "4_4") (pintype "passive"))
      (node (ref "R4") (pin "1") (pinfunction "1_1") (pintype "passive"))
    )
    (net (code "4") (name "1.1V") (class "Default")
      (node (ref "C49") (pin "1") (pinfunction "1_1") (pintype "passive"))
      (node (ref "C50") (pin "1") (pinfunction "1_1") (pintype "passive"))
      (node (ref "C51") (pin "1") (pinfunction "1_1") (pintype "passive"))
      (node (ref "U7") (pin "23") (pinfunction "VDD_1V1_23") (pintype "bidirectional"))
      (node (ref "U7") (pin "45") (pinfunction "LDO_OUT_45") (pintype "bidirectional"))
      (node (ref "U7") (pin "50") (pinfunction "VDD_1V1_50") (pintype "bidirectional"))
    )
    (net (code "5") (name "ALRT") (class "Default")
      (node (ref "R25") (pin "1") (pinfunction "1_1") (pintype "passive"))
      (node (ref "U1") (pin "5") (pinfunction "~{ALERT}_5") (pintype "output"))
    )
    (net (code "6") (name "AVDD") (class "Default")
      (node (ref "C53") (pin "1") (pinfunction "1_1") (pintype "passive"))
      (node (ref "R24") (pin "1") (pinfunction "1_1") (pintype "passive"))
      (node (ref "U7") (pin "43") (pinfunction "ADC_VDD_43") (pintype "bidirectional"))
    )
    (net (code "7") (name "BOOT") (class "Default")
      (node (ref "R21") (pin "2") (pinfunction "2_2") (pintype "passive"))
      (node (ref "SW4") (pin "B'") (pinfunction "S1_B'") (pintype "passive"))
      (node (ref "U$24") (pin "2") (pinfunction "1_2") (pintype "passive"))
    )
    (net (code "8") (name "CHR_STUS") (class "Default")
      (node (ref "R48") (pin "1") (pinfunction "1_1") (pintype "passive"))
      (node (ref "U5") (pin "1") (pinfunction "STAT_1") (pintype "output"))
    )
    (net (code "9") (name "D+") (class "Default")
      (node (ref "J5") (pin "A6") (pinfunction "D+_A6") (pintype "bidirectional"))
      (node (ref "J5") (pin "B6") (pinfunction "D+_B6") (pintype "bidirectional"))
      (node (ref "R8") (pin "1") (pinfunction "1_1") (pintype "passive"))
      (node (ref "U8") (pin "5") (pinfunction "IO4_5") (pintype "bidirectional"))
    )
    (net (code "10") (name "D-") (class "Default")
      (node (ref "J5") (pin "A7") (pinfunction "D-_A7") (pintype "bidirectional"))
      (node (ref "J5") (pin "B7") (pinfunction "D-_B7") (pintype "bidirectional"))
      (node (ref "R10") (pin "1") (pinfunction "1_1") (pintype "passive"))
      (node (ref "U8") (pin "4") (pinfunction "IO3_4") (pintype "bidirectional"))
    )
    (net (code "11") (name "ECGN") (class "Default")
      (node (ref "C43") (pin "1") (pinfunction "1_1") (pintype "passive"))
      (node (ref "C45") (pin "2") (pinfunction "2_2") (pintype "passive"))
      (node (ref "R40") (pin "2") (pinfunction "2_2") (pintype "passive"))
      (node (ref "U$30") (pin "A6") (pinfunction "INN_A6") (pintype "bidirectional"))
    )
    (net (code "12") (name "ECGN1") (class "Default")
      (node (ref "C66") (pin "1") (pinfunction "1_1") (pintype "passive"))
      (node (ref "JP3") (pin "TIP") (pinfunction "LEFT_TIP") (pintype "bidirectional"))
      (node (ref "R40") (pin "1") (pinfunction "1_1") (pintype "passive"))
      (node (ref "R42") (pin "1") (pinfunction "1_1") (pintype "passive"))
    )
    (net (code "13") (name "ECGP") (class "Default")
      (node (ref "C44") (pin "1") (pinfunction "1_1") (pintype "passive"))
      (node (ref "C45") (pin "1") (pinfunction "1_1") (pintype "passive"))
      (node (ref "R39") (pin "2") (pinfunction "2_2") (pintype "passive"))
      (node (ref "U$30") (pin "A5") (pinfunction "INP_A5") (pintype "bidirectional"))
    )
    (net (code "14") (name "ECGP1") (class "Default")
      (node (ref "C63") (pin "1") (pinfunction "1_1") (pintype "passive"))
      (node (ref "JP3") (pin "RING") (pinfunction "RIGHT_RING") (pintype "bidirectional"))
      (node (ref "R39") (pin "1") (pinfunction "1_1") (pintype "passive"))
      (node (ref "R43") (pin "1") (pinfunction "1_1") (pintype "passive"))
    )
    (net (code "15") (name "ECG_CS") (class "Default")
      (node (ref "U$30") (pin "E6") (pinfunction "CSB_E6") (pintype "bidirectional"))
      (node (ref "U7") (pin "7") (pinfunction "GPIO5_7") (pintype "bidirectional"))
    )
    (net (code "16") (name "ECG_VCM") (class "Default")
      (node (ref "C33") (pin "1") (pinfunction "1_1") (pintype "passive"))
      (node (ref "R41") (pin "1") (pinfunction "1_1") (pintype "passive"))
      (node (ref "U$30") (pin "C1") (pinfunction "VCM_C1") (pintype "bidirectional"))
    )
    (net (code "17") (name "EN") (class "Default")
      (node (ref "K1") (pin "29") (pinfunction "29_29") (pintype "passive"))
      (node (ref "S2") (pin "2") (pinfunction "2-_C_2") (pintype "bidirectional"))
      (node (ref "U$26") (pin "3") (pinfunction "EN_3") (pintype "bidirectional"))
      (node (ref "U3") (pin "3") (pinfunction "EN_3") (pintype "input"))
    )
    (net (code "18") (name "ESP32_CS") (class "Default")
      (node (ref "U4") (pin "16") (pinfunction "IO10_16") (pintype "bidirectional"))
      (node (ref "U7") (pin "12") (pinfunction "GPIO9_12") (pintype "bidirectional"))
    )
    (net (code "19") (name "ESP32_SD_TFT_MISO") (class "Default")
      (node (ref "J4") (pin "7") (pinfunction "DATA0_7") (pintype "bidirectional"))
      (node (ref "K1") (pin "21") (pinfunction "21_21") (pintype "passive"))
      (node (ref "R2") (pin "1") (pinfunction "1_1") (pintype "passive"))
      (node (ref "U7") (pin "11") (pinfunction "GPIO8_11") (pintype "bidirectional"))
    )
    (net (code "20") (name "ESP32_SD_TFT_MOSI") (class "Default")
      (node (ref "J4") (pin "3") (pinfunction "CMD_3") (pintype "bidirectional"))
      (node (ref "K1") (pin "19") (pinfunction "19_19") (pintype "passive"))
      (node (ref "U7") (pin "14") (pinfunction "GPIO11_14") (pintype "bidirectional"))
    )
    (net (code "21") (name "ESP32_SD_TFT_SCK") (class "Default")
      (node (ref "J4") (pin "5") (pinfunction "CLK_5") (pintype "bidirectional"))
      (node (ref "K1") (pin "23") (pinfunction "23_23") (pintype "passive"))
      (node (ref "U7") (pin "13") (pinfunction "GPIO10_13") (pintype "bidirectional"))
    )
    (net (code "22") (name "ESP32_UART_CTS") (class "Default")
      (node (ref "U4") (pin "19") (pinfunction "IO5_19") (pintype "bidirectional"))
      (node (ref "U7") (pin "39") (pinfunction "GPIO27/ADC1_39") (pintype "bidirectional"))
    )
    (net (code "23") (name "ESP32_UART_RTS") (class "Default")
      (node (ref "U4") (pin "18") (pinfunction "IO4_18") (pintype "bidirectional"))
      (node (ref "U7") (pin "38") (pinfunction "GPIO26/ADC0_38") (pintype "bidirectional"))
    )
    (net (code "24") (name "ESP32_UART_RXD") (class "Default")
      (node (ref "R37") (pin "2") (pinfunction "2_2") (pintype "passive"))
      (node (ref "U4") (pin "21") (pinfunction "IO7_21") (pintype "bidirectional"))
    )
    (net (code "25") (name "ESP32_UART_TXD") (class "Default")
      (node (ref "R36") (pin "2") (pinfunction "2_2") (pintype "passive"))
      (node (ref "U4") (pin "20") (pinfunction "IO6_20") (pintype "bidirectional"))
    )
    (net (code "26") (name "ESP_BOOT") (class "Default")
      (node (ref "SW1") (pin "B'") (pinfunction "S1_B'") (pintype "passive"))
      (node (ref "U4") (pin "23") (pinfunction "IO9_23") (pintype "bidirectional"))
    )
    (net (code "27") (name "ESP_RST") (class "Default")
      (node (ref "C4") (pin "2") (pinfunction "2_2") (pintype "passive"))
      (node (ref "R23") (pin "1") (pinfunction "1_1") (pintype "passive"))
      (node (ref "SW2") (pin "B'") (pinfunction "S1_B'") (pintype "passive"))
      (node (ref "U4") (pin "8") (pinfunction "EN_8") (pintype "input"))
    )
    (net (code "28") (name "FCLK") (class "Default")
      (node (ref "TP2") (pin "P$1") (pinfunction "1_P$1") (pintype "bidirectional"))
      (node (ref "U$30") (pin "D5") (pinfunction "FCLK_D5") (pintype "bidirectional"))
      (node (ref "U$31") (pin "3") (pinfunction "CLK_3") (pintype "bidirectional"))
    )
    (net (code "29") (name "GND") (class "Default")
      (node (ref "C1") (pin "2") (pinfunction "2_2") (pintype "passive"))
      (node (ref "C10") (pin "2") (pinfunction "2_2") (pintype "passive"))
      (node (ref "C11") (pin "2") (pinfunction "2_2") (pintype "passive"))
      (node (ref "C12") (pin "2") (pinfunction "2_2") (pintype "passive"))
      (node (ref "C13") (pin "2") (pinfunction "2_2") (pintype "passive"))
      (node (ref "C14") (pin "2") (pinfunction "2_2") (pintype "passive"))
      (node (ref "C15") (pin "1") (pinfunction "1_1") (pintype "passive"))
      (node (ref "C16") (pin "2") (pinfunction "2_2") (pintype "passive"))
      (node (ref "C18") (pin "2") (pinfunction "2_2") (pintype "passive"))
      (node (ref "C19") (pin "2") (pinfunction "2_2") (pintype "passive"))
      (node (ref "C2") (pin "2") (pinfunction "2_2") (pintype "passive"))
      (node (ref "C22") (pin "2") (pinfunction "2_2") (pintype "passive"))
      (node (ref "C24") (pin "2") (pinfunction "2_2") (pintype "passive"))
      (node (ref "C25") (pin "2") (pinfunction "2_2") (pintype "passive"))
      (node (ref "C27") (pin "2") (pinfunction "2_2") (pintype "passive"))
      (node (ref "C28") (pin "2") (pinfunction "2_2") (pintype "passive"))
      (node (ref "C29") (pin "2") (pinfunction "2_2") (pintype "passive"))
      (node (ref "C3") (pin "1") (pinfunction "1_1") (pintype "passive"))
      (node (ref "C30") (pin "2") (pinfunction "2_2") (pintype "passive"))
      (node (ref "C31") (pin "1") (pinfunction "1_1") (pintype "passive"))
      (node (ref "C32") (pin "2") (pinfunction "2_2") (pintype "passive"))
      (node (ref "C33") (pin "2") (pinfunction "2_2") (pintype "passive"))
      (node (ref "C34") (pin "2") (pinfunction "2_2") (pintype "passive"))
      (node (ref "C35") (pin "1") (pinfunction "1_1") (pintype "passive"))
      (node (ref "C36") (pin "1") (pinfunction "1_1") (pintype "passive"))
      (node (ref "C37") (pin "1") (pinfunction "1_1") (pintype "passive"))
      (node (ref "C38") (pin "2") (pinfunction "2_2") (pintype "passive"))
      (node (ref "C39") (pin "2") (pinfunction "2_2") (pintype "passive"))
      (node (ref "C4") (pin "1") (pinfunction "1_1") (pintype "passive"))
      (node (ref "C40") (pin "2") (pinfunction "2_2") (pintype "passive"))
      (node (ref "C41") (pin "2") (pinfunction "2_2") (pintype "passive"))
      (node (ref "C42") (pin "2") (pinfunction "2_2") (pintype "passive"))
      (node (ref "C43") (pin "2") (pinfunction "2_2") (pintype "passive"))
      (node (ref "C44") (pin "2") (pinfunction "2_2") (pintype "passive"))
      (node (ref "C46") (pin "2") (pinfunction "2_2") (pintype "passive"))
      (node (ref "C47") (pin "2") (pinfunction "2_2") (pintype "passive"))
      (node (ref "C48") (pin "2") (pinfunction "2_2") (pintype "passive"))
      (node (ref "C49") (pin "2") (pinfunction "2_2") (pintype "passive"))
      (node (ref "C5") (pin "2") (pinfunction "2_2") (pintype "passive"))
      (node (ref "C50") (pin "2") (pinfunction "2_2") (pintype "passive"))
      (node (ref "C51") (pin "2") (pinfunction "2_2") (pintype "passive"))
      (node (ref "C52") (pin "2") (pinfunction "2_2") (pintype "passive"))
      (node (ref "C53") (pin "2") (pinfunction "2_2") (pintype "passive"))
      (node (ref "C59") (pin "2") (pinfunction "2_2") (pintype "passive"))
      (node (ref "C6") (pin "1") (pinfunction "1_1") (pintype "passive"))
      (node (ref "C64") (pin "2") (pinfunction "2_2") (pintype "passive"))
      (node (ref "C65") (pin "2") (pinfunction "2_2") (pintype "passive"))
      (node (ref "C67") (pin "2") (pinfunction "2_2") (pintype "passive"))
      (node (ref "C68") (pin "2") (pinfunction "2_2") (pintype "passive"))
      (node (ref "C7") (pin "1") (pinfunction "1_1") (pintype "passive"))
      (node (ref "C70") (pin "2") (pinfunction "P$2_2") (pintype "passive"))
      (node (ref "C8") (pin "2") (pinfunction "2_2") (pintype "passive"))
      (node (ref "C9") (pin "2") (pinfunction "2_2") (pintype "passive"))
      (node (ref "D1") (pin "2") (pinfunction "C_2") (pintype "passive"))
      (node (ref "D2") (pin "2") (pinfunction "C_2") (pintype "passive"))
      (node (ref "D3") (pin "2") (pinfunction "C_2") (pintype "passive"))
      (node (ref "D5") (pin "2") (pinfunction "C_2") (pintype "passive"))
      (node (ref "D6") (pin "A") (pinfunction "A_A") (pintype "passive"))
      (node (ref "J1") (pin "1") (pinfunction "1_1") (pintype "power_in"))
      (node (ref "J3") (pin "GND") (pinfunction "GND_GND") (pintype "bidirectional"))
      (node (ref "J3") (pin "GND2") (pinfunction "GND_GND2") (pintype "bidirectional"))
      (node (ref "J3") (pin "SHLD1") (pinfunction "SHLD_SHLD1") (pintype "bidirectional"))
      (node (ref "J3") (pin "SHLD2") (pinfunction "SHLD_SHLD2") (pintype "bidirectional"))
      (node (ref "J3") (pin "SHLD3") (pinfunction "SHLD_SHLD3") (pintype "bidirectional"))
      (node (ref "J3") (pin "SHLD4") (pinfunction "SHLD_SHLD4") (pintype "bidirectional"))
      (node (ref "J3") (pin "SHLD5") (pinfunction "SHLD_SHLD5") (pintype "bidirectional"))
      (node (ref "J3") (pin "SHLD6") (pinfunction "SHLD_SHLD6") (pintype "bidirectional"))
      (node (ref "J3") (pin "SHLD7") (pinfunction "SHLD_SHLD7") (pintype "bidirectional"))
      (node (ref "J3") (pin "SHLD8") (pinfunction "SHLD_SHLD8") (pintype "bidirectional"))
      (node (ref "J4") (pin "6") (pinfunction "VSS_6") (pintype "power_in"))
      (node (ref "J5") (pin "GND") (pinfunction "GND_GND") (pintype "bidirectional"))
      (node (ref "J5") (pin "GND2") (pinfunction "GND_GND2") (pintype "bidirectional"))
      (node (ref "J5") (pin "SHLD1") (pinfunction "SHLD_SHLD1") (pintype "bidirectional"))
      (node (ref "J5") (pin "SHLD2") (pinfunction "SHLD_SHLD2") (pintype "bidirectional"))
      (node (ref "J5") (pin "SHLD3") (pinfunction "SHLD_SHLD3") (pintype "bidirectional"))
      (node (ref "J5") (pin "SHLD4") (pinfunction "SHLD_SHLD4") (pintype "bidirectional"))
      (node (ref "J5") (pin "SHLD5") (pinfunction "SHLD_SHLD5") (pintype "bidirectional"))
      (node (ref "J5") (pin "SHLD6") (pinfunction "SHLD_SHLD6") (pintype "bidirectional"))
      (node (ref "J5") (pin "SHLD7") (pinfunction "SHLD_SHLD7") (pintype "bidirectional"))
      (node (ref "J5") (pin "SHLD8") (pinfunction "SHLD_SHLD8") (pintype "bidirectional"))
      (node (ref "J6") (pin "2") (pinfunction "2_2") (pintype "passive"))
      (node (ref "J6") (pin "S1") (pinfunction "SHIELD_S1") (pintype "passive"))
      (node (ref "J6") (pin "S2") (pinfunction "SHIELD_S2") (pintype "passive"))
      (node (ref "J7") (pin "2") (pinfunction "2_2") (pintype "passive"))
      (node (ref "J7") (pin "S1") (pinfunction "SHIELD_S1") (pintype "passive"))
      (node (ref "J7") (pin "S2") (pinfunction "SHIELD_S2") (pintype "passive"))
      (node (ref "JP6") (pin "1") (pinfunction "1_1") (pintype "passive"))
      (node (ref "K1") (pin "14") (pinfunction "14_14") (pintype "passive"))
      (node (ref "K1") (pin "20") (pinfunction "20_20") (pintype "passive"))
      (node (ref "K1") (pin "25") (pinfunction "25_25") (pintype "passive"))
      (node (ref "K1") (pin "30") (pinfunction "30_30") (pintype "passive"))
      (node (ref "K1") (pin "34") (pinfunction "34_34") (pintype "passive"))
      (node (ref "K1") (pin "39") (pinfunction "39_39") (pintype "passive"))
      (node (ref "K1") (pin "6") (pinfunction "6_6") (pintype "passive"))
      (node (ref "K1") (pin "9") (pinfunction "9_9") (pintype "passive"))
      (node (ref "R1") (pin "1") (pinfunction "1_1") (pintype "passive"))
      (node (ref "R11") (pin "1") (pinfunction "1_1") (pintype "passive"))
      (node (ref "R15") (pin "2") (pinfunction "2_2") (pintype "passive"))
      (node (ref "R16") (pin "2") (pinfunction "2_2") (pintype "passive"))
      (node (ref "R26") (pin "2") (pinfunction "2_2") (pintype "passive"))
      (node (ref "R27") (pin "2") (pinfunction "2_2") (pintype "passive"))
      (node (ref "R30") (pin "1") (pinfunction "1_1") (pintype "passive"))
      (node (ref "R44") (pin "2") (pinfunction "2_2") (pintype "passive"))
      (node (ref "SW1") (pin "A'") (pinfunction "P1_A'") (pintype "passive"))
      (node (ref "SW2") (pin "A'") (pinfunction "P1_A'") (pintype "passive"))
      (node (ref "SW4") (pin "A'") (pinfunction "P1_A'") (pintype "passive"))
      (node (ref "SW5") (pin "A'") (pinfunction "P1_A'") (pintype "passive"))
      (node (ref "U$24") (pin "3") (pinfunction "0_3") (pintype "passive"))
      (node (ref "U$26") (pin "2") (pinfunction "GND_2") (pintype "bidirectional"))
      (node (ref "U$3") (pin "12") (pinfunction "LED_DRV_GND_12") (pintype "bidirectional"))
      (node (ref "U$3") (pin "13") (pinfunction "LED_DRV_GND_13") (pintype "bidirectional"))
      (node (ref "U$3") (pin "16") (pinfunction "LED_DRV_GND_16") (pintype "bidirectional"))
      (node (ref "U$3") (pin "19") (pinfunction "RX_DIG_GND_19") (pintype "bidirectional"))
      (node (ref "U$3") (pin "3") (pinfunction "RX_ANA_GND_3") (pintype "bidirectional"))
      (node (ref "U$3") (pin "32") (pinfunction "RX_DIG_GND_32") (pintype "bidirectional"))
      (node (ref "U$3") (pin "36") (pinfunction "RX_ANA_GND_36") (pintype "bidirectional"))
      (node (ref "U$3") (pin "40") (pinfunction "RX_ANA_GND_40") (pintype "bidirectional"))
      (node (ref "U$3") (pin "8") (pinfunction "VSS_8") (pintype "bidirectional"))
      (node (ref "U$3") (pin "EXP@10") (pinfunction "THER3_EXP@10") (pintype "bidirectional"))
      (node (ref "U$3") (pin "EXP@11") (pinfunction "THER4_EXP@11") (pintype "bidirectional"))
      (node (ref "U$3") (pin "EXP@6") (pinfunction "THER1_EXP@6") (pintype "bidirectional"))
      (node (ref "U$3") (pin "EXP@7") (pinfunction "THER2_EXP@7") (pintype "bidirectional"))
      (node (ref "U$30") (pin "B3") (pinfunction "AGND_B3") (pintype "bidirectional"))
      (node (ref "U$30") (pin "B4") (pinfunction "AGND_B4") (pintype "bidirectional"))
      (node (ref "U$30") (pin "C3") (pinfunction "AGND_C3") (pintype "bidirectional"))
      (node (ref "U$30") (pin "C4") (pinfunction "AGND_C4") (pintype "bidirectional"))
      (node (ref "U$30") (pin "C5") (pinfunction "DGND_C5") (pintype "bidirectional"))
      (node (ref "U$30") (pin "D4") (pinfunction "AGND_D4") (pintype "bidirectional"))
      (node (ref "U$31") (pin "2") (pinfunction "GND_2") (pintype "bidirectional"))
      (node (ref "U$38") (pin "4") (pinfunction "GND_4") (pintype "bidirectional"))
      (node (ref "U$38") (pin "9") (pinfunction "EP_9") (pintype "bidirectional"))
      (node (ref "U1") (pin "1") (pinfunction "CTG_1") (pintype "power_in"))
      (node (ref "U1") (pin "4") (pinfunction "GND_4") (pintype "power_in"))
      (node (ref "U1") (pin "6") (pinfunction "QSTRT_6") (pintype "input"))
      (node (ref "U1") (pin "9") (pinfunction "EP_9") (pintype "power_in"))
      (node (ref "U3") (pin "2") (pinfunction "GND_2") (pintype "input"))
      (node (ref "U4") (pin "1") (pinfunction "GND_1") (pintype "power_in"))
      (node (ref "U4") (pin "11") (pinfunction "GND_11") (pintype "power_in"))
      (node (ref "U4") (pin "14") (pinfunction "GND_14") (pintype "power_in"))
      (node (ref "U4") (pin "2") (pinfunction "GND_2") (pintype "power_in"))
      (node (ref "U4") (pin "36") (pinfunction "GND_36") (pintype "power_in"))
      (node (ref "U4") (pin "37") (pinfunction "GND_37") (pintype "power_in"))
      (node (ref "U4") (pin "38") (pinfunction "GND_38") (pintype "power_in"))
      (node (ref "U4") (pin "39") (pinfunction "GND_39") (pintype "power_in"))
      (node (ref "U4") (pin "40") (pinfunction "GND_40") (pintype "power_in"))
      (node (ref "U4") (pin "41") (pinfunction "GND_41") (pintype "power_in"))
      (node (ref "U4") (pin "42") (pinfunction "GND_42") (pintype "power_in"))
      (node (ref "U4") (pin "43") (pinfunction "GND_43") (pintype "power_in"))
      (node (ref "U4") (pin "44") (pinfunction "GND_44") (pintype "power_in"))
      (node (ref "U4") (pin "45") (pinfunction "GND_45") (pintype "power_in"))
      (node (ref "U4") (pin "46") (pinfunction "GND_46") (pintype "power_in"))
      (node (ref "U4") (pin "47") (pinfunction "GND_47") (pintype "power_in"))
      (node (ref "U4") (pin "48") (pinfunction "GND_48") (pintype "power_in"))
      (node (ref "U4") (pin "49_1") (pinfunction "GND_49_1") (pintype "power_in"))
      (node (ref "U4") (pin "49_2") (pinfunction "GND_49_2") (pintype "power_in"))
      (node (ref "U4") (pin "49_3") (pinfunction "GND_49_3") (pintype "power_in"))
      (node (ref "U4") (pin "49_4") (pinfunction "GND_49_4") (pintype "power_in"))
      (node (ref "U4") (pin "49_5") (pinfunction "GND_49_5") (pintype "power_in"))
      (node (ref "U4") (pin "49_6") (pinfunction "GND_49_6") (pintype "power_in"))
      (node (ref "U4") (pin "49_7") (pinfunction "GND_49_7") (pintype "power_in"))
      (node (ref "U4") (pin "49_8") (pinfunction "GND_49_8") (pintype "power_in"))
      (node (ref "U4") (pin "49_9") (pinfunction "GND_49_9") (pintype "power_in"))
      (node (ref "U4") (pin "50") (pinfunction "GND_50") (pintype "power_in"))
      (node (ref "U4") (pin "51") (pinfunction "GND_51") (pintype "power_in"))
      (node (ref "U4") (pin "52") (pinfunction "GND_52") (pintype "power_in"))
      (node (ref "U4") (pin "53") (pinfunction "GND_53") (pintype "power_in"))
      (node (ref "U5") (pin "2") (pinfunction "VSS_2") (pintype "power_in"))
      (node (ref "U6") (pin "4") (pinfunction "GND_4") (pintype "bidirectional"))
      (node (ref "U7") (pin "19") (pinfunction "TESTEN_19") (pintype "bidirectional"))
      (node (ref "U7") (pin "EPAD") (pinfunction "GND_EPAD") (pintype "bidirectional"))
      (node (ref "U8") (pin "3") (pinfunction "GND_3") (pintype "power_in"))
      (node (ref "X1") (pin "7") (pinfunction "7_7") (pintype "passive"))
      (node (ref "X1") (pin "G1") (pinfunction "P$1_G1") (pintype "bidirectional"))
      (node (ref "X1") (pin "G2") (pinfunction "P$2_G2") (pintype "bidirectional"))
    )
    (net (code "30") (name "INN") (class "Default")
      (node (ref "D3") (pin "1") (pinfunction "CA_1") (pintype "passive"))
      (node (ref "U$3") (pin "1") (pinfunction "INN_1") (pintype "bidirectional"))
      (node (ref "X1") (pin "5") (pinfunction "5_5") (pintype "passive"))
    )
    (net (code "31") (name "INP") (class "Default")
      (node (ref "D2") (pin "1") (pinfunction "CA_1") (pintype "passive"))
      (node (ref "U$3") (pin "2") (pinfunction "INP_2") (pintype "bidirectional"))
      (node (ref "X1") (pin "9") (pinfunction "9_9") (pintype "passive"))
    )
    (net (code "32") (name "INT2B") (class "Default")
      (node (ref "U$30") (pin "E2") (pinfunction "INT2B_E2") (pintype "bidirectional"))
    )
    (net (code "33") (name "INTB") (class "Default")
      (node (ref "U$30") (pin "D2") (pinfunction "INTB_D2") (pintype "bidirectional"))
      (node (ref "U7") (pin "31") (pinfunction "GPIO20_31") (pintype "bidirectional"))
    )
    (net (code "34") (name "LED1") (class "Default")
      (node (ref "R51") (pin "2") (pinfunction "2_2") (pintype "passive"))
      (node (ref "U7") (pin "34") (pinfunction "GPIO22_34") (pintype "bidirectional"))
    )
    (net (code "35") (name "LED2") (class "Default")
      (node (ref "R49") (pin "1") (pinfunction "1_1") (pintype "passive"))
      (node (ref "U7") (pin "32") (pinfunction "GPIO21_32") (pintype "bidirectional"))
    )
    (net (code "36") (name "LED_DRV_SUP") (class "Default")
      (node (ref "C10") (pin "1") (pinfunction "1_1") (pintype "passive"))
      (node (ref "C28") (pin "1") (pinfunction "1_1") (pintype "passive"))
      (node (ref "D1") (pin "3") (pinfunction "A_3") (pintype "passive"))
      (node (ref "D5") (pin "3") (pinfunction "A_3") (pintype "passive"))
      (node (ref "U$11") (pin "2") (pinfunction "P$2_2") (pintype "bidirectional"))
      (node (ref "U$3") (pin "17") (pinfunction "LED_DRV_SUP_17") (pintype "bidirectional"))
      (node (ref "U$3") (pin "18") (pinfunction "LED_DRV_SUP_18") (pintype "bidirectional"))
    )
    (net (code "37") (name "MISO") (class "Default")
      (node (ref "U$3") (pin "25") (pinfunction "SPISOMI_25") (pintype "bidirectional"))
      (node (ref "U$30") (pin "E3") (pinfunction "SDO_E3") (pintype "bidirectional"))
      (node (ref "U7") (pin "6") (pinfunction "GPIO4_6") (pintype "bidirectional"))
    )
    (net (code "38") (name "MOSI") (class "Default")
      (node (ref "U$3") (pin "26") (pinfunction "SPISIMO_26") (pintype "bidirectional"))
      (node (ref "U$30") (pin "E4") (pinfunction "SDI_E4") (pintype "bidirectional"))
      (node (ref "U7") (pin "5") (pinfunction "GPIO3_5") (pintype "bidirectional"))
    )
    (net (code "39") (name "Net-(J3-CC1)") (class "Default")
      (node (ref "J3") (pin "A5") (pinfunction "CC1_A5") (pintype "bidirectional"))
      (node (ref "R27") (pin "1") (pinfunction "1_1") (pintype "passive"))
    )
    (net (code "40") (name "Net-(J3-CC2)") (class "Default")
      (node (ref "J3") (pin "B5") (pinfunction "CC2_B5") (pintype "bidirectional"))
      (node (ref "R26") (pin "1") (pinfunction "1_1") (pintype "passive"))
    )
    (net (code "41") (name "Net-(J5-CC1)") (class "Default")
      (node (ref "J5") (pin "A5") (pinfunction "CC1_A5") (pintype "bidirectional"))
      (node (ref "R16") (pin "1") (pinfunction "1_1") (pintype "passive"))
    )
    (net (code "42") (name "Net-(J5-CC2)") (class "Default")
      (node (ref "J5") (pin "B5") (pinfunction "CC2_B5") (pintype "bidirectional"))
      (node (ref "R15") (pin "1") (pinfunction "1_1") (pintype "passive"))
    )
    (net (code "43") (name "Net-(JP3-PadSLEEVE)") (class "Default")
      (node (ref "JP3") (pin "SLEEVE") (pinfunction "SLEEVE_SLEEVE") (pintype "bidirectional"))
      (node (ref "R41") (pin "2") (pinfunction "2_2") (pintype "passive"))
    )
    (net (code "44") (name "Net-(JP_SW3-Pad3)") (class "Default")
      (node (ref "JP_SW3") (pin "3") (pinfunction "3_3") (pintype "passive"))
      (node (ref "K1") (pin "16") (pinfunction "16_16") (pintype "passive"))
    )
    (net (code "45") (name "Net-(LED1-0)") (class "Default")
      (node (ref "LED1") (pin "1") (pinfunction "0_1") (pintype "passive"))
      (node (ref "LED1") (pin "2") (pinfunction "1_2") (pintype "passive"))
      (node (ref "R49") (pin "2") (pinfunction "2_2") (pintype "passive"))
    )
    (net (code "46") (name "Net-(LED1-3)") (class "Default")
      (node (ref "LED1") (pin "4") (pinfunction "3_4") (pintype "passive"))
      (node (ref "R48") (pin "2") (pinfunction "2_2") (pintype "passive"))
    )
    (net (code "47") (name "Net-(LED1-5)") (class "Default")
      (node (ref "LED1") (pin "6") (pinfunction "5_6") (pintype "passive"))
      (node (ref "R51") (pin "1") (pinfunction "1_1") (pintype "passive"))
    )
    (net (code "48") (name "Net-(Q3-S)") (class "Default")
      (node (ref "C22") (pin "1") (pinfunction "1_1") (pintype "passive"))
      (node (ref "C37") (pin "2") (pinfunction "2_2") (pintype "passive"))
      (node (ref "D10") (pin "C") (pinfunction "C_C") (pintype "passive"))
      (node (ref "Q3") (pin "2") (pinfunction "S_2") (pintype "passive"))
      (node (ref "S2") (pin "3") (pinfunction "3_3") (pintype "bidirectional"))
      (node (ref "U$26") (pin "1") (pinfunction "VIN_1") (pintype "bidirectional"))
      (node (ref "U3") (pin "1") (pinfunction "IN_1") (pintype "input"))
    )
    (net (code "49") (name "Net-(R1-Pad2)") (class "Default")
      (node (ref "R1") (pin "2") (pinfunction "2_2") (pintype "passive"))
      (node (ref "S2") (pin "1") (pinfunction "1_1") (pintype "bidirectional"))
    )
    (net (code "50") (name "Net-(TP4-1)") (class "Default")
      (node (ref "TP4") (pin "P$1") (pinfunction "1_P$1") (pintype "bidirectional"))
      (node (ref "U$3") (pin "30") (pinfunction "CLKOUT_30") (pintype "bidirectional"))
    )
    (net (code "51") (name "Net-(U$3-BG)") (class "Default")
      (node (ref "C8") (pin "1") (pinfunction "1_1") (pintype "passive"))
      (node (ref "U$3") (pin "7") (pinfunction "BG_7") (pintype "bidirectional"))
    )
    (net (code "52") (name "Net-(U$3-XIN)") (class "Default")
      (node (ref "C6") (pin "2") (pinfunction "2_2") (pintype "passive"))
      (node (ref "U$3") (pin "38") (pinfunction "XIN_38") (pintype "bidirectional"))
      (node (ref "U$4") (pin "2") (pinfunction "2_2") (pintype "passive"))
    )
    (net (code "53") (name "Net-(U$3-XOUT)") (class "Default")
      (node (ref "C7") (pin "2") (pinfunction "2_2") (pintype "passive"))
      (node (ref "U$3") (pin "37") (pinfunction "XOUT_37") (pintype "bidirectional"))
      (node (ref "U$4") (pin "1") (pinfunction "1_1") (pintype "passive"))
    )
    (net (code "54") (name "Net-(U$19-1)") (class "Default")
      (node (ref "C1") (pin "1") (pinfunction "1_1") (pintype "passive"))
      (node (ref "U$19") (pin "P$1") (pinfunction "1_P$1") (pintype "passive"))
      (node (ref "U4") (pin "13") (pinfunction "IO1_13") (pintype "bidirectional"))
    )
    (net (code "55") (name "Net-(U$19-2)") (class "Default")
      (node (ref "C15") (pin "2") (pinfunction "2_2") (pintype "passive"))
      (node (ref "U$19") (pin "P$2") (pinfunction "2_P$2") (pintype "passive"))
      (node (ref "U4") (pin "12") (pinfunction "IO0_12") (pintype "bidirectional"))
    )
    (net (code "56") (name "Net-(U$30-BIN)") (class "Default")
      (node (ref "C67") (pin "1") (pinfunction "1_1") (pintype "passive"))
      (node (ref "C69") (pin "1") (pinfunction "1_1") (pintype "passive"))
      (node (ref "R42") (pin "2") (pinfunction "2_2") (pintype "passive"))
      (node (ref "U$30") (pin "A3") (pinfunction "BIN_A3") (pintype "bidirectional"))
    )
    (net (code "57") (name "Net-(U$30-BIP)") (class "Default")
      (node (ref "C68") (pin "1") (pinfunction "1_1") (pintype "passive"))
      (node (ref "C69") (pin "2") (pinfunction "2_2") (pintype "passive"))
      (node (ref "R43") (pin "2") (pinfunction "2_2") (pintype "passive"))
      (node (ref "U$30") (pin "A4") (pinfunction "BIP_A4") (pintype "bidirectional"))
    )
    (net (code "58") (name "Net-(U$30-CAPN)") (class "Default")
      (node (ref "C26") (pin "2") (pinfunction "2_2") (pintype "passive"))
      (node (ref "U$30") (pin "B5") (pinfunction "CAPN_B5") (pintype "bidirectional"))
    )
    (net (code "59") (name "Net-(U$30-CAPP)") (class "Default")
      (node (ref "C26") (pin "1") (pinfunction "1_1") (pintype "passive"))
      (node (ref "U$30") (pin "B6") (pinfunction "CAPP_B6") (pintype "bidirectional"))
    )
    (net (code "60") (name "Net-(U$30-CPLL)") (class "Default")
      (node (ref "C29") (pin "1") (pinfunction "1_1") (pintype "passive"))
      (node (ref "U$30") (pin "C6") (pinfunction "CPLL_C6") (pintype "bidirectional"))
    )
    (net (code "61") (name "Net-(U$30-DRVN)") (class "Default")
      (node (ref "C66") (pin "2") (pinfunction "2_2") (pintype "passive"))
      (node (ref "U$30") (pin "A2") (pinfunction "DRVN_A2") (pintype "bidirectional"))
    )
    (net (code "62") (name "Net-(U$30-DRVP)") (class "Default")
      (node (ref "C63") (pin "2") (pinfunction "2_2") (pintype "passive"))
      (node (ref "U$30") (pin "A1") (pinfunction "DRVP_A1") (pintype "bidirectional"))
    )
    (net (code "63") (name "Net-(U$30-RBIAS)") (class "Default")
      (node (ref "R44") (pin "1") (pinfunction "1_1") (pintype "passive"))
      (node (ref "U$30") (pin "B2") (pinfunction "RBIAS_B2") (pintype "bidirectional"))
    )
    (net (code "64") (name "Net-(U$30-VBG)") (class "Default")
      (node (ref "C34") (pin "1") (pinfunction "1_1") (pintype "passive"))
      (node (ref "U$30") (pin "B1") (pinfunction "VBG_B1") (pintype "bidirectional"))
    )
    (net (code "65") (name "Net-(U$30-VREF)") (class "Default")
      (node (ref "C32") (pin "1") (pinfunction "1_1") (pintype "passive"))
      (node (ref "U$30") (pin "D1") (pinfunction "VREF_D1") (pintype "bidirectional"))
    )
    (net (code "66") (name "Net-(U4-IO2)") (class "Default")
      (node (ref "R2") (pin "2") (pinfunction "2_2") (pintype "passive"))
      (node (ref "U4") (pin "5") (pinfunction "IO2_5") (pintype "bidirectional"))
    )
    (net (code "67") (name "Net-(U4-IO3)") (class "Default")
      (node (ref "SWIO3") (pin "TP") (pinfunction "TP_TP") (pintype "input"))
      (node (ref "U4") (pin "6") (pinfunction "IO3_6") (pintype "bidirectional"))
    )
    (net (code "68") (name "Net-(U4-IO8)") (class "Default")
      (node (ref "SWIO2") (pin "TP") (pinfunction "TP_TP") (pintype "input"))
      (node (ref "U4") (pin "22") (pinfunction "IO8_22") (pintype "bidirectional"))
    )
    (net (code "69") (name "Net-(U4-RXD0)") (class "Default")
      (node (ref "SWIO8") (pin "TP") (pinfunction "TP_TP") (pintype "input"))
      (node (ref "U4") (pin "30") (pinfunction "RXD0_30") (pintype "bidirectional"))
    )
    (net (code "70") (name "Net-(U4-TXD0)") (class "Default")
      (node (ref "SWIO9") (pin "TP") (pinfunction "TP_TP") (pintype "input"))
      (node (ref "U4") (pin "31") (pinfunction "TXD0_31") (pintype "bidirectional"))
    )
    (net (code "71") (name "Net-(U5-PROG)") (class "Default")
      (node (ref "R11") (pin "2") (pinfunction "2_2") (pintype "passive"))
      (node (ref "U5") (pin "5") (pinfunction "PROG_5") (pintype "input"))
    )
    (net (code "72") (name "Net-(U7-GPIO0)") (class "Default")
      (node (ref "R3") (pin "1") (pinfunction "1_1") (pintype "passive"))
      (node (ref "U7") (pin "2") (pinfunction "GPIO0_2") (pintype "bidirectional"))
    )
    (net (code "73") (name "Net-(U7-GPIO1)") (class "Default")
      (node (ref "R6") (pin "1") (pinfunction "1_1") (pintype "passive"))
      (node (ref "U7") (pin "3") (pinfunction "GPIO1_3") (pintype "bidirectional"))
    )
    (net (code "74") (name "Net-(U7-GPIO24)") (class "Default")
      (node (ref "R37") (pin "1") (pinfunction "1_1") (pintype "passive"))
      (node (ref "U7") (pin "36") (pinfunction "GPIO24_36") (pintype "bidirectional"))
    )
    (net (code "75") (name "Net-(U7-GPIO25)") (class "Default")
      (node (ref "R36") (pin "1") (pinfunction "1_1") (pintype "passive"))
      (node (ref "U7") (pin "37") (pinfunction "GPIO25_37") (pintype "bidirectional"))
    )
    (net (code "76") (name "Net-(U7-SWCLK)") (class "Default")
      (node (ref "R9") (pin "2") (pinfunction "2_2") (pintype "passive"))
      (node (ref "U7") (pin "24") (pinfunction "SWCLK_24") (pintype "bidirectional"))
    )
    (net (code "77") (name "Net-(U7-SWDIO)") (class "Default")
      (node (ref "R12") (pin "2") (pinfunction "2_2") (pintype "passive"))
      (node (ref "U7") (pin "25") (pinfunction "SWDIO_25") (pintype "bidirectional"))
    )
    (net (code "78") (name "Net-(U7-USB_D+)") (class "Default")
      (node (ref "R20") (pin "2") (pinfunction "2_2") (pintype "passive"))
      (node (ref "U7") (pin "47") (pinfunction "USB_D+_47") (pintype "bidirectional"))
    )
    (net (code "79") (name "Net-(U7-USB_D-)") (class "Default")
      (node (ref "R19") (pin "2") (pinfunction "2_2") (pintype "passive"))
      (node (ref "U7") (pin "46") (pinfunction "USB_D-_46") (pintype "bidirectional"))
    )
    (net (code "80") (name "Net-(U7-XIN)") (class "Default")
      (node (ref "C36") (pin "2") (pinfunction "2_2") (pintype "passive"))
      (node (ref "U7") (pin "20") (pinfunction "XIN_20") (pintype "bidirectional"))
      (node (ref "Y2") (pin "P3") (pinfunction "2_P3") (pintype "passive"))
    )
    (net (code "81") (name "Net-(U7-XOUT)") (class "Default")
      (node (ref "R18") (pin "2") (pinfunction "2_2") (pintype "passive"))
      (node (ref "U7") (pin "21") (pinfunction "XOUT_21") (pintype "bidirectional"))
    )
    (net (code "82") (name "Net-(Y2-1)") (class "Default")
      (node (ref "C31") (pin "2") (pinfunction "2_2") (pintype "passive"))
      (node (ref "R18") (pin "1") (pinfunction "1_1") (pintype "passive"))
      (node (ref "Y2") (pin "P1") (pinfunction "1_P1") (pintype "passive"))
    )
    (net (code "83") (name "QSPI-0") (class "Default")
      (node (ref "U6") (pin "5") (pinfunction "D0/DI_5") (pintype "bidirectional"))
      (node (ref "U7") (pin "53") (pinfunction "QSPI_SD0_53") (pintype "bidirectional"))
    )
    (net (code "84") (name "QSPI-1") (class "Default")
      (node (ref "U6") (pin "2") (pinfunction "D1/DO_2") (pintype "bidirectional"))
      (node (ref "U7") (pin "55") (pinfunction "QSPI_SD1_55") (pintype "bidirectional"))
    )
    (net (code "85") (name "QSPI-2") (class "Default")
      (node (ref "U6") (pin "3") (pinfunction "D2/~{WP}_3") (pintype "bidirectional"))
      (node (ref "U7") (pin "54") (pinfunction "QSPI_SD2_54") (pintype "bidirectional"))
    )
    (net (code "86") (name "QSPI-3") (class "Default")
      (node (ref "U6") (pin "7") (pinfunction "D3/~{HOLD}_7") (pintype "bidirectional"))
      (node (ref "U7") (pin "51") (pinfunction "QSPI_SD3_51") (pintype "bidirectional"))
    )
    (net (code "87") (name "QSPI-CLK") (class "Default")
      (node (ref "U6") (pin "6") (pinfunction "CLK_6") (pintype "bidirectional"))
      (node (ref "U7") (pin "52") (pinfunction "QSPI_SCLK_52") (pintype "bidirectional"))
    )
    (net (code "88") (name "QSPI-CS") (class "Default")
      (node (ref "R21") (pin "1") (pinfunction "1_1") (pintype "passive"))
      (node (ref "R22") (pin "1") (pinfunction "1_1") (pintype "passive"))
      (node (ref "U6") (pin "1") (pinfunction "~{CS}_1") (pintype "bidirectional"))
      (node (ref "U7") (pin "56") (pinfunction "QSPI_~{CS}_56") (pintype "bidirectional"))
    )
    (net (code "89") (name "RP_D+") (class "Default")
      (node (ref "J3") (pin "A6") (pinfunction "D+_A6") (pintype "bidirectional"))
      (node (ref "J3") (pin "B6") (pinfunction "D+_B6") (pintype "bidirectional"))
      (node (ref "R20") (pin "1") (pinfunction "1_1") (pintype "passive"))
      (node (ref "U8") (pin "1") (pinfunction "IO1_1") (pintype "bidirectional"))
    )
    (net (code "90") (name "RP_D-") (class "Default")
      (node (ref "J3") (pin "A7") (pinfunction "D-_A7") (pintype "bidirectional"))
      (node (ref "J3") (pin "B7") (pinfunction "D-_B7") (pintype "bidirectional"))
      (node (ref "R19") (pin "1") (pinfunction "1_1") (pintype "passive"))
      (node (ref "U8") (pin "2") (pinfunction "IO2_2") (pintype "bidirectional"))
    )
    (net (code "91") (name "RX_ANA_SUP") (class "Default")
      (node (ref "C11") (pin "1") (pinfunction "1_1") (pintype "passive"))
      (node (ref "C18") (pin "1") (pinfunction "1_1") (pintype "passive"))
      (node (ref "D2") (pin "3") (pinfunction "A_3") (pintype "passive"))
      (node (ref "D3") (pin "3") (pinfunction "A_3") (pintype "passive"))
      (node (ref "U$3") (pin "33") (pinfunction "RX_ANA_SUP_33") (pintype "bidirectional"))
      (node (ref "U$3") (pin "39") (pinfunction "RX_ANA_SUP_39") (pintype "bidirectional"))
      (node (ref "U$7") (pin "2") (pinfunction "P$2_2") (pintype "bidirectional"))
    )
    (net (code "92") (name "RX_DIG_SUP") (class "Default")
      (node (ref "C12") (pin "1") (pinfunction "1_1") (pintype "passive"))
      (node (ref "C19") (pin "1") (pinfunction "1_1") (pintype "passive"))
      (node (ref "R47") (pin "1") (pinfunction "1_1") (pintype "passive"))
      (node (ref "U$3") (pin "31") (pinfunction "RX_DIG_SUP_31") (pintype "bidirectional"))
      (node (ref "U$9") (pin "2") (pinfunction "P$2_2") (pintype "bidirectional"))
    )
    (net (code "93") (name "SCK") (class "Default")
      (node (ref "U$3") (pin "24") (pinfunction "SCLK_24") (pintype "bidirectional"))
      (node (ref "U$30") (pin "E5") (pinfunction "SCLK_E5") (pintype "bidirectional"))
      (node (ref "U7") (pin "4") (pinfunction "GPIO2_4") (pintype "bidirectional"))
    )
    (net (code "94") (name "SD_CS") (class "Default")
      (node (ref "J4") (pin "2") (pinfunction "DATA3/CD_2") (pintype "bidirectional"))
      (node (ref "R5") (pin "1") (pinfunction "1_1") (pintype "passive"))
      (node (ref "U7") (pin "16") (pinfunction "GPIO13_16") (pintype "bidirectional"))
    )
    (net (code "95") (name "SPO2_CS") (class "Default")
      (node (ref "U$3") (pin "27") (pinfunction "SPISTE_27") (pintype "bidirectional"))
      (node (ref "U7") (pin "30") (pinfunction "GPIO19_30") (pintype "bidirectional"))
    )
    (net (code "96") (name "SPO2_DRDY") (class "Default")
      (node (ref "U$3") (pin "28") (pinfunction "ADC_RDY_28") (pintype "bidirectional"))
      (node (ref "U7") (pin "28") (pinfunction "GPIO17_28") (pintype "bidirectional"))
    )
    (net (code "97") (name "SPO2_START") (class "Default")
      (node (ref "U$3") (pin "20") (pinfunction "AFE_~{PDN}_20") (pintype "bidirectional"))
      (node (ref "U7") (pin "29") (pinfunction "GPIO18_29") (pintype "bidirectional"))
    )
    (net (code "98") (name "SW1") (class "Default")
      (node (ref "K1") (pin "26") (pinfunction "26_26") (pintype "passive"))
      (node (ref "U7") (pin "15") (pinfunction "GPIO12_15") (pintype "bidirectional"))
    )
    (net (code "99") (name "SW2") (class "Default")
      (node (ref "K1") (pin "31") (pinfunction "31_31") (pintype "passive"))
      (node (ref "U7") (pin "17") (pinfunction "GPIO14_17") (pintype "bidirectional"))
    )
    (net (code "100") (name "SW3") (class "Default")
      (node (ref "JP_SW3") (pin "2") (pinfunction "2_2") (pintype "passive"))
      (node (ref "U7") (pin "18") (pinfunction "GPIO15_18") (pintype "bidirectional"))
    )
    (net (code "101") (name "SWDCK") (class "Default")
      (node (ref "J6") (pin "1") (pinfunction "1_1") (pintype "passive"))
      (node (ref "R9") (pin "1") (pinfunction "1_1") (pintype "passive"))
    )
    (net (code "102") (name "SWDIO") (class "Default")
      (node (ref "J6") (pin "3") (pinfunction "3_3") (pintype "passive"))
      (node (ref "R12") (pin "1") (pinfunction "1_1") (pintype "passive"))
    )
    (net (code "103") (name "TFT_BKL") (class "Default")
      (node (ref "K1") (pin "12") (pinfunction "12_12") (pintype "passive"))
      (node (ref "U7") (pin "27") (pinfunction "GPIO16_27") (pintype "bidirectional"))
    )
    (net (code "104") (name "TFT_CS") (class "Default")
      (node (ref "K1") (pin "24") (pinfunction "24_24") (pintype "passive"))
      (node (ref "U7") (pin "41") (pinfunction "GPIO29/ADC3_41") (pintype "bidirectional"))
    )
    (net (code "105") (name "TFT_DC") (class "Default")
      (node (ref "K1") (pin "22") (pinfunction "22_22") (pintype "passive"))
      (node (ref "U7") (pin "35") (pinfunction "GPIO23_35") (pintype "bidirectional"))
    )
    (net (code "106") (name "TFT_RESET") (class "Default")
      (node (ref "K1") (pin "36") (pinfunction "36_36") (pintype "passive"))
      (node (ref "U7") (pin "40") (pinfunction "GPIO28/ADC2_40") (pintype "bidirectional"))
    )
    (net (code "107") (name "TMP_SCL") (class "Default")
      (node (ref "J1") (pin "4") (pinfunction "4_4") (pintype "passive"))
      (node (ref "K1") (pin "5") (pinfunction "5_5") (pintype "passive"))
      (node (ref "R7") (pin "2") (pinfunction "2_2") (pintype "passive"))
      (node (ref "U$38") (pin "6") (pinfunction "SCL_6") (pintype "bidirectional"))
      (node (ref "U1") (pin "7") (pinfunction "SCL_7") (pintype "input"))
      (node (ref "U7") (pin "9") (pinfunction "GPIO7_9") (pintype "bidirectional"))
    )
    (net (code "108") (name "TMP_SDA") (class "Default")
      (node (ref "J1") (pin "3") (pinfunction "3_3") (pintype "passive"))
      (node (ref "K1") (pin "3") (pinfunction "3_3") (pintype "passive"))
      (node (ref "R33") (pin "2") (pinfunction "2_2") (pintype "passive"))
      (node (ref "U$38") (pin "5") (pinfunction "SDA_5") (pintype "bidirectional"))
      (node (ref "U1") (pin "8") (pinfunction "SDA_8") (pintype "bidirectional"))
      (node (ref "U7") (pin "8") (pinfunction "GPIO6_8") (pintype "bidirectional"))
    )
    (net (code "109") (name "TXN") (class "Default")
      (node (ref "D1") (pin "1") (pinfunction "CA_1") (pintype "passive"))
      (node (ref "U$3") (pin "14") (pinfunction "TXN_14") (pintype "bidirectional"))
      (node (ref "X1") (pin "3") (pinfunction "3_3") (pintype "passive"))
    )
    (net (code "110") (name "TXP") (class "Default")
      (node (ref "D5") (pin "1") (pinfunction "CA_1") (pintype "passive"))
      (node (ref "U$3") (pin "15") (pinfunction "TXP_15") (pintype "bidirectional"))
      (node (ref "X1") (pin "2") (pinfunction "2_2") (pintype "passive"))
    )
    (net (code "111") (name "TX_CTRL_SUP") (class "Default")
      (node (ref "C27") (pin "1") (pinfunction "1_1") (pintype "passive"))
      (node (ref "C9") (pin "1") (pinfunction "1_1") (pintype "passive"))
      (node (ref "U$10") (pin "2") (pinfunction "P$2_2") (pintype "bidirectional"))
      (node (ref "U$3") (pin "11") (pinfunction "TX_CTRL_SUP_11") (pintype "bidirectional"))
    )
    (net (code "112") (name "U0RXD") (class "Default")
      (node (ref "J7") (pin "1") (pinfunction "1_1") (pintype "passive"))
      (node (ref "JP_SW3") (pin "1") (pinfunction "1_1") (pintype "passive"))
      (node (ref "K1") (pin "8") (pinfunction "8_8") (pintype "passive"))
      (node (ref "R6") (pin "2") (pinfunction "2_2") (pintype "passive"))
    )
    (net (code "113") (name "U0TXD") (class "Default")
      (node (ref "J7") (pin "3") (pinfunction "3_3") (pintype "passive"))
      (node (ref "K1") (pin "10") (pinfunction "10_10") (pintype "passive"))
      (node (ref "R3") (pin "2") (pinfunction "2_2") (pintype "passive"))
    )
    (net (code "114") (name "USB_D+") (class "Default")
      (node (ref "R8") (pin "2") (pinfunction "2_2") (pintype "passive"))
      (node (ref "U4") (pin "27") (pinfunction "IO19_27") (pintype "bidirectional"))
    )
    (net (code "115") (name "USB_D-") (class "Default")
      (node (ref "R10") (pin "2") (pinfunction "2_2") (pintype "passive"))
      (node (ref "U4") (pin "26") (pinfunction "IO18_26") (pintype "bidirectional"))
    )
    (net (code "116") (name "VBAT") (class "Default")
      (node (ref "C5") (pin "1") (pinfunction "1_1") (pintype "passive"))
      (node (ref "C65") (pin "1") (pinfunction "1_1") (pintype "passive"))
      (node (ref "JP6") (pin "2") (pinfunction "2_2") (pintype "passive"))
      (node (ref "Q3") (pin "3") (pinfunction "D_3") (pintype "passive"))
      (node (ref "U1") (pin "2") (pinfunction "CELL_2") (pintype "power_in"))
      (node (ref "U1") (pin "3") (pinfunction "VDD_3") (pintype "power_in"))
      (node (ref "U5") (pin "3") (pinfunction "VBAT_3") (pintype "power_in"))
    )
    (net (code "117") (name "VBUS") (class "Default")
      (node (ref "D6") (pin "C") (pinfunction "C_C") (pintype "passive"))
      (node (ref "D9") (pin "A") (pinfunction "A_A") (pintype "passive"))
      (node (ref "J3") (pin "VBUS1") (pinfunction "VBUS_VBUS1") (pintype "bidirectional"))
      (node (ref "J3") (pin "VBUS2") (pinfunction "VBUS_VBUS2") (pintype "bidirectional"))
      (node (ref "J5") (pin "VBUS1") (pinfunction "VBUS_VBUS1") (pintype "bidirectional"))
      (node (ref "J5") (pin "VBUS2") (pinfunction "VBUS_VBUS2") (pintype "bidirectional"))
      (node (ref "TP5") (pin "TP") (pinfunction "TP_TP") (pintype "input"))
      (node (ref "U8") (pin "6") (pinfunction "VCC_6") (pintype "power_in"))
    )
    (net (code "118") (name "VCM") (class "Default")
      (node (ref "C13") (pin "1") (pinfunction "1_1") (pintype "passive"))
      (node (ref "U$3") (pin "4") (pinfunction "VCM_4") (pintype "bidirectional"))
    )
    (net (code "119") (name "VDD") (class "Default")
      (node (ref "C64") (pin "1") (pinfunction "1_1") (pintype "passive"))
      (node (ref "D10") (pin "A") (pinfunction "A_A") (pintype "passive"))
      (node (ref "D8") (pin "C") (pinfunction "C_C") (pintype "passive"))
      (node (ref "D9") (pin "C") (pinfunction "C_C") (pintype "passive"))
      (node (ref "LED1") (pin "5") (pinfunction "4_5") (pintype "passive"))
      (node (ref "Q3") (pin "1") (pinfunction "G_1") (pintype "passive"))
      (node (ref "R30") (pin "2") (pinfunction "2_2") (pintype "passive"))
      (node (ref "R4") (pin "2") (pinfunction "2_2") (pintype "passive"))
      (node (ref "SWIO7") (pin "TP") (pinfunction "TP_TP") (pintype "input"))
      (node (ref "U5") (pin "4") (pinfunction "VIN_4") (pintype "power_in"))
    )
    (net (code "120") (name "unconnected-(J4-DATA1-Pad8)") (class "Default")
      (node (ref "J4") (pin "8") (pinfunction "DATA1_8") (pintype "bidirectional"))
    )
    (net (code "121") (name "unconnected-(J4-DATA2-Pad1)") (class "Default")
      (node (ref "J4") (pin "1") (pinfunction "DATA2_1") (pintype "bidirectional"))
    )
    (net (code "122") (name "unconnected-(J4-DETECH-Pad9)") (class "Default")
      (node (ref "J4") (pin "9") (pinfunction "DETECH_9") (pintype "passive"))
    )
    (net (code "123") (name "unconnected-(K1-Pad7)") (class "Default")
      (node (ref "K1") (pin "7") (pinfunction "7_7") (pintype "passive"))
    )
    (net (code "124") (name "unconnected-(K1-Pad11)") (class "Default")
      (node (ref "K1") (pin "11") (pinfunction "11_11") (pintype "passive"))
    )
    (net (code "125") (name "unconnected-(K1-Pad13)") (class "Default")
      (node (ref "K1") (pin "13") (pinfunction "13_13") (pintype "passive"))
    )
    (net (code "126") (name "unconnected-(K1-Pad15)") (class "Default")
      (node (ref "K1") (pin "15") (pinfunction "15_15") (pintype "passive"))
    )
    (net (code "127") (name "unconnected-(K1-Pad18)") (class "Default")
      (node (ref "K1") (pin "18") (pinfunction "18_18") (pintype "passive"))
    )
    (net (code "128") (name "unconnected-(K1-Pad27)") (class "Default")
      (node (ref "K1") (pin "27") (pinfunction "27_27") (pintype "passive"))
    )
    (net (code "129") (name "unconnected-(K1-Pad28)") (class "Default")
      (node (ref "K1") (pin "28") (pinfunction "28_28") (pintype "passive"))
    )
    (net (code "130") (name "unconnected-(K1-Pad32)") (class "Default")
      (node (ref "K1") (pin "32") (pinfunction "32_32") (pintype "passive"))
    )
    (net (code "131") (name "unconnected-(K1-Pad33)") (class "Default")
      (node (ref "K1") (pin "33") (pinfunction "33_33") (pintype "passive"))
    )
    (net (code "132") (name "unconnected-(K1-Pad35)") (class "Default")
      (node (ref "K1") (pin "35") (pinfunction "35_35") (pintype "passive"))
    )
    (net (code "133") (name "unconnected-(K1-Pad37)") (class "Default")
      (node (ref "K1") (pin "37") (pinfunction "37_37") (pintype "passive"))
    )
    (net (code "134") (name "unconnected-(K1-Pad38)") (class "Default")
      (node (ref "K1") (pin "38") (pinfunction "38_38") (pintype "passive"))
    )
    (net (code "135") (name "unconnected-(K1-Pad40)") (class "Default")
      (node (ref "K1") (pin "40") (pinfunction "40_40") (pintype "passive"))
    )
    (net (code "136") (name "unconnected-(S2-5-Pad4)") (class "Default")
      (node (ref "S2") (pin "4") (pinfunction "5_4") (pintype "bidirectional"))
    )
    (net (code "137") (name "unconnected-(S2-6_-_C-Pad5)") (class "Default")
      (node (ref "S2") (pin "5") (pinfunction "6_-_C_5") (pintype "bidirectional"))
    )
    (net (code "138") (name "unconnected-(S2-7-Pad6)") (class "Default")
      (node (ref "S2") (pin "6") (pinfunction "7_6") (pintype "bidirectional"))
    )
    (net (code "139") (name "unconnected-(SW1-P-PadA)") (class "Default")
      (node (ref "SW1") (pin "A") (pinfunction "P_A") (pintype "passive"))
    )
    (net (code "140") (name "unconnected-(SW1-S-PadB)") (class "Default")
      (node (ref "SW1") (pin "B") (pinfunction "S_B") (pintype "passive"))
    )
    (net (code "141") (name "unconnected-(SW2-P-PadA)") (class "Default")
      (node (ref "SW2") (pin "A") (pinfunction "P_A") (pintype "passive"))
    )
    (net (code "142") (name "unconnected-(SW2-S-PadB)") (class "Default")
      (node (ref "SW2") (pin "B") (pinfunction "S_B") (pintype "passive"))
    )
    (net (code "143") (name "unconnected-(SW4-P-PadA)") (class "Default")
      (node (ref "SW4") (pin "A") (pinfunction "P_A") (pintype "passive"))
    )
    (net (code "144") (name "unconnected-(SW4-S-PadB)") (class "Default")
      (node (ref "SW4") (pin "B") (pinfunction "S_B") (pintype "passive"))
    )
    (net (code "145") (name "unconnected-(SW5-P-PadA)") (class "Default")
      (node (ref "SW5") (pin "A") (pinfunction "P_A") (pintype "passive"))
    )
    (net (code "146") (name "unconnected-(SW5-S-PadB)") (class "Default")
      (node (ref "SW5") (pin "B") (pinfunction "S_B") (pintype "passive"))
    )
    (net (code "147") (name "unconnected-(U$3-DIAG_END-Pad21)") (class "Default")
      (node (ref "U$3") (pin "21") (pinfunction "DIAG_END_21") (pintype "bidirectional"))
    )
    (net (code "148") (name "unconnected-(U$3-DNC-Pad5)") (class "Default")
      (node (ref "U$3") (pin "5") (pinfunction "DNC_5") (pintype "bidirectional"))
    )
    (net (code "149") (name "unconnected-(U$3-DNC-Pad6)") (class "Default")
      (node (ref "U$3") (pin "6") (pinfunction "DNC_6") (pintype "bidirectional"))
    )
    (net (code "150") (name "unconnected-(U$3-DNC-Pad10)") (class "Default")
      (node (ref "U$3") (pin "10") (pinfunction "DNC_10") (pintype "bidirectional"))
    )
    (net (code "151") (name "unconnected-(U$3-DNC-Pad34)") (class "Default")
      (node (ref "U$3") (pin "34") (pinfunction "DNC_34") (pintype "bidirectional"))
    )
    (net (code "152") (name "unconnected-(U$3-DNC-Pad35)") (class "Default")
      (node (ref "U$3") (pin "35") (pinfunction "DNC_35") (pintype "bidirectional"))
    )
    (net (code "153") (name "unconnected-(U$3-LED_ALM-Pad22)") (class "Default")
      (node (ref "U$3") (pin "22") (pinfunction "LED_ALM_22") (pintype "bidirectional"))
    )
    (net (code "154") (name "unconnected-(U$3-PD_ALM-Pad23)") (class "Default")
      (node (ref "U$3") (pin "23") (pinfunction "PD_ALM_23") (pintype "bidirectional"))
    )
    (net (code "155") (name "unconnected-(U$3-RSVD-Pad9)") (class "Default")
      (node (ref "U$3") (pin "9") (pinfunction "RSVD_9") (pintype "bidirectional"))
    )
    (net (code "156") (name "unconnected-(U$24-0-Pad1)") (class "Default")
      (node (ref "U$24") (pin "1") (pinfunction "0_1") (pintype "passive"))
    )
    (net (code "157") (name "unconnected-(U$24-1-Pad4)") (class "Default")
      (node (ref "U$24") (pin "4") (pinfunction "1_4") (pintype "passive"))
    )
    (net (code "158") (name "unconnected-(U$26-NC-Pad4)") (class "Default")
      (node (ref "U$26") (pin "4") (pinfunction "NC_4") (pintype "bidirectional"))
    )
    (net (code "159") (name "unconnected-(U$30-AOUT-PadC2)") (class "Default")
      (node (ref "U$30") (pin "C2") (pinfunction "AOUT_C2") (pintype "bidirectional"))
    )
    (net (code "160") (name "unconnected-(U$31-NC-Pad1)") (class "Default")
      (node (ref "U$31") (pin "1") (pinfunction "NC_1") (pintype "bidirectional"))
    )
    (net (code "161") (name "unconnected-(U$38-NC-Pad1)") (class "Default")
      (node (ref "U$38") (pin "1") (pinfunction "NC_1") (pintype "bidirectional"))
    )
    (net (code "162") (name "unconnected-(U$38-NC-Pad2)") (class "Default")
      (node (ref "U$38") (pin "2") (pinfunction "NC_2") (pintype "bidirectional"))
    )
    (net (code "163") (name "unconnected-(U$38-NC-Pad3)") (class "Default")
      (node (ref "U$38") (pin "3") (pinfunction "NC_3") (pintype "bidirectional"))
    )
    (net (code "164") (name "unconnected-(U$38-NC-Pad7)") (class "Default")
      (node (ref "U$38") (pin "7") (pinfunction "NC_7") (pintype "bidirectional"))
    )
    (net (code "165") (name "unconnected-(U3-BP-Pad4)") (class "Default")
      (node (ref "U3") (pin "4") (pinfunction "BP_4") (pintype "input"))
    )
    (net (code "166") (name "unconnected-(U4-NC-Pad4)") (class "Default")
      (node (ref "U4") (pin "4") (pinfunction "NC_4") (pintype "no_connect"))
    )
    (net (code "167") (name "unconnected-(U4-NC-Pad7)") (class "Default")
      (node (ref "U4") (pin "7") (pinfunction "NC_7") (pintype "no_connect"))
    )
    (net (code "168") (name "unconnected-(U4-NC-Pad9)") (class "Default")
      (node (ref "U4") (pin "9") (pinfunction "NC_9") (pintype "no_connect"))
    )
    (net (code "169") (name "unconnected-(U4-NC-Pad10)") (class "Default")
      (node (ref "U4") (pin "10") (pinfunction "NC_10") (pintype "no_connect"))
    )
    (net (code "170") (name "unconnected-(U4-NC-Pad15)") (class "Default")
      (node (ref "U4") (pin "15") (pinfunction "NC_15") (pintype "no_connect"))
    )
    (net (code "171") (name "unconnected-(U4-NC-Pad17)") (class "Default")
      (node (ref "U4") (pin "17") (pinfunction "NC_17") (pintype "no_connect"))
    )
    (net (code "172") (name "unconnected-(U4-NC-Pad24)") (class "Default")
      (node (ref "U4") (pin "24") (pinfunction "NC_24") (pintype "no_connect"))
    )
    (net (code "173") (name "unconnected-(U4-NC-Pad25)") (class "Default")
      (node (ref "U4") (pin "25") (pinfunction "NC_25") (pintype "no_connect"))
    )
    (net (code "174") (name "unconnected-(U4-NC-Pad28)") (class "Default")
      (node (ref "U4") (pin "28") (pinfunction "NC_28") (pintype "no_connect"))
    )
    (net (code "175") (name "unconnected-(U4-NC-Pad29)") (class "Default")
      (node (ref "U4") (pin "29") (pinfunction "NC_29") (pintype "no_connect"))
    )
    (net (code "176") (name "unconnected-(U4-NC-Pad32)") (class "Default")
      (node (ref "U4") (pin "32") (pinfunction "NC_32") (pintype "no_connect"))
    )
    (net (code "177") (name "unconnected-(U4-NC-Pad33)") (class "Default")
      (node (ref "U4") (pin "33") (pinfunction "NC_33") (pintype "no_connect"))
    )
    (net (code "178") (name "unconnected-(U4-NC-Pad34)") (class "Default")
      (node (ref "U4") (pin "34") (pinfunction "NC_34") (pintype "no_connect"))
    )
    (net (code "179") (name "unconnected-(U4-NC-Pad35)") (class "Default")
      (node (ref "U4") (pin "35") (pinfunction "NC_35") (pintype "no_connect"))
    )
    (net (code "180") (name "unconnected-(X1-Pad1)") (class "Default")
      (node (ref "X1") (pin "1") (pinfunction "1_1") (pintype "passive"))
    )
    (net (code "181") (name "unconnected-(X1-Pad4)") (class "Default")
      (node (ref "X1") (pin "4") (pinfunction "4_4") (pintype "passive"))
    )
    (net (code "182") (name "unconnected-(X1-Pad6)") (class "Default")
      (node (ref "X1") (pin "6") (pinfunction "6_6") (pintype "passive"))
    )
    (net (code "183") (name "unconnected-(X1-Pad8)") (class "Default")
      (node (ref "X1") (pin "8") (pinfunction "8_8") (pintype "passive"))
    )
    (net (code "184") (name "~{ADC_RESET}") (class "Default")
      (node (ref "R47") (pin "2") (pinfunction "2_2") (pintype "passive"))
      (node (ref "U$3") (pin "29") (pinfunction "~{RESET}_29") (pintype "bidirectional"))
    )
    (net (code "185") (name "~{RESET}") (class "Default")
      (node (ref "SW5") (pin "B'") (pinfunction "S1_B'") (pintype "passive"))
      (node (ref "U7") (pin "26") (pinfunction "RUN_26") (pintype "bidirectional"))
    )
  )
)
